# ESP32_Watch-2_01_inch_V1_0.net
KiCad netlist of a schematic drawn in EAGLE
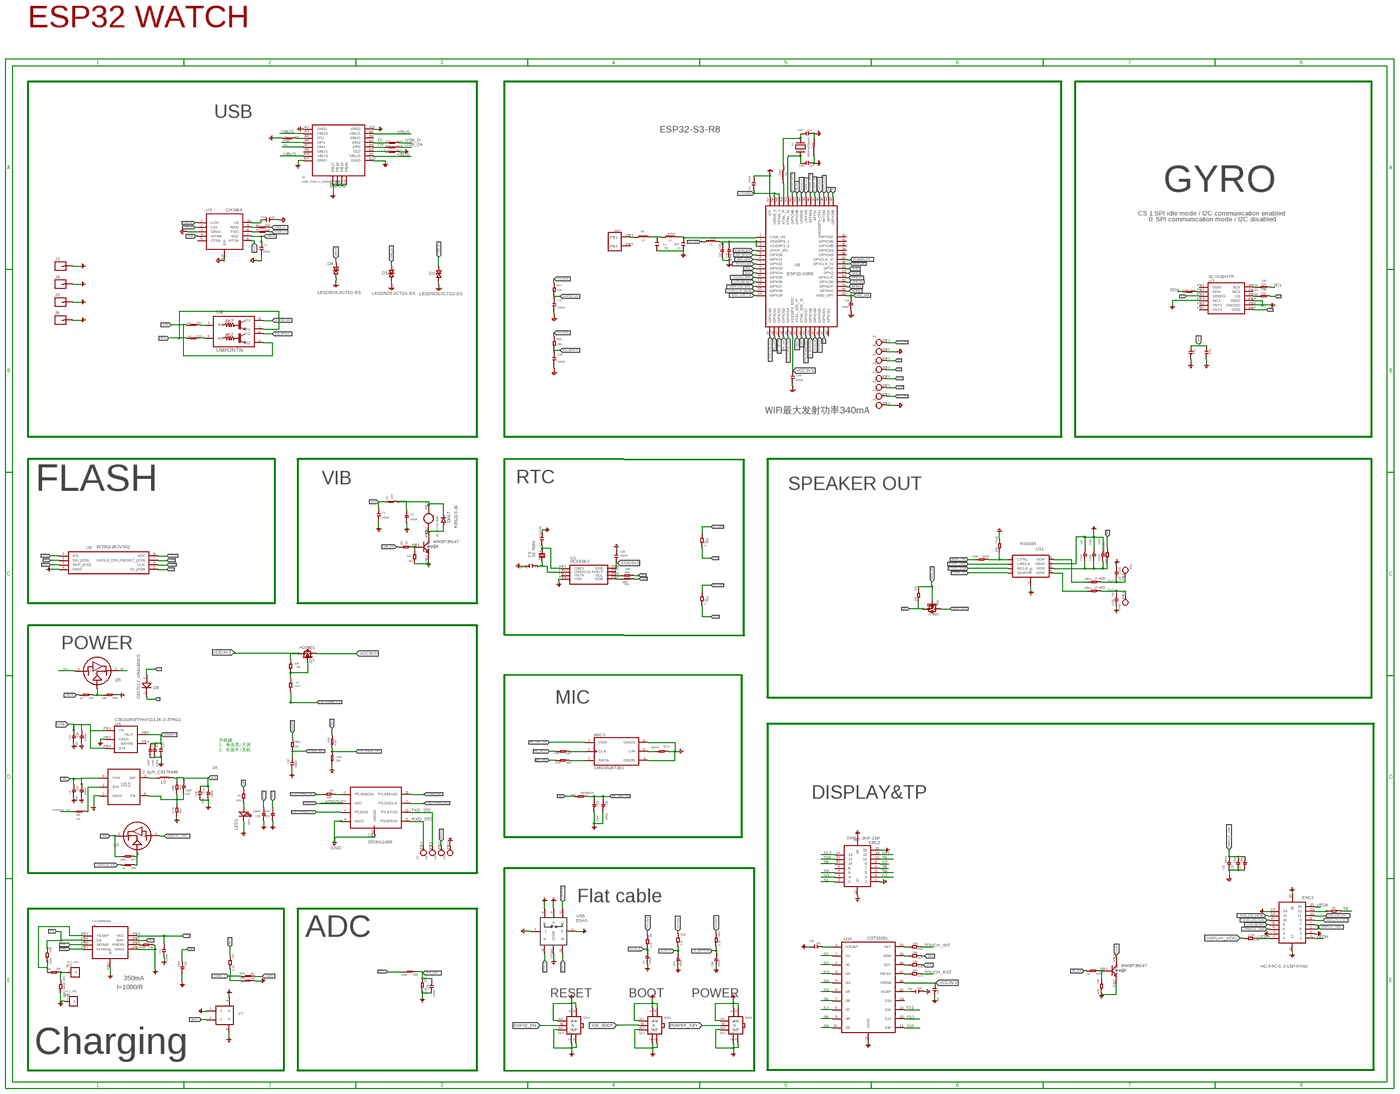
[diagram p0: schematic, sheet 1, overview]
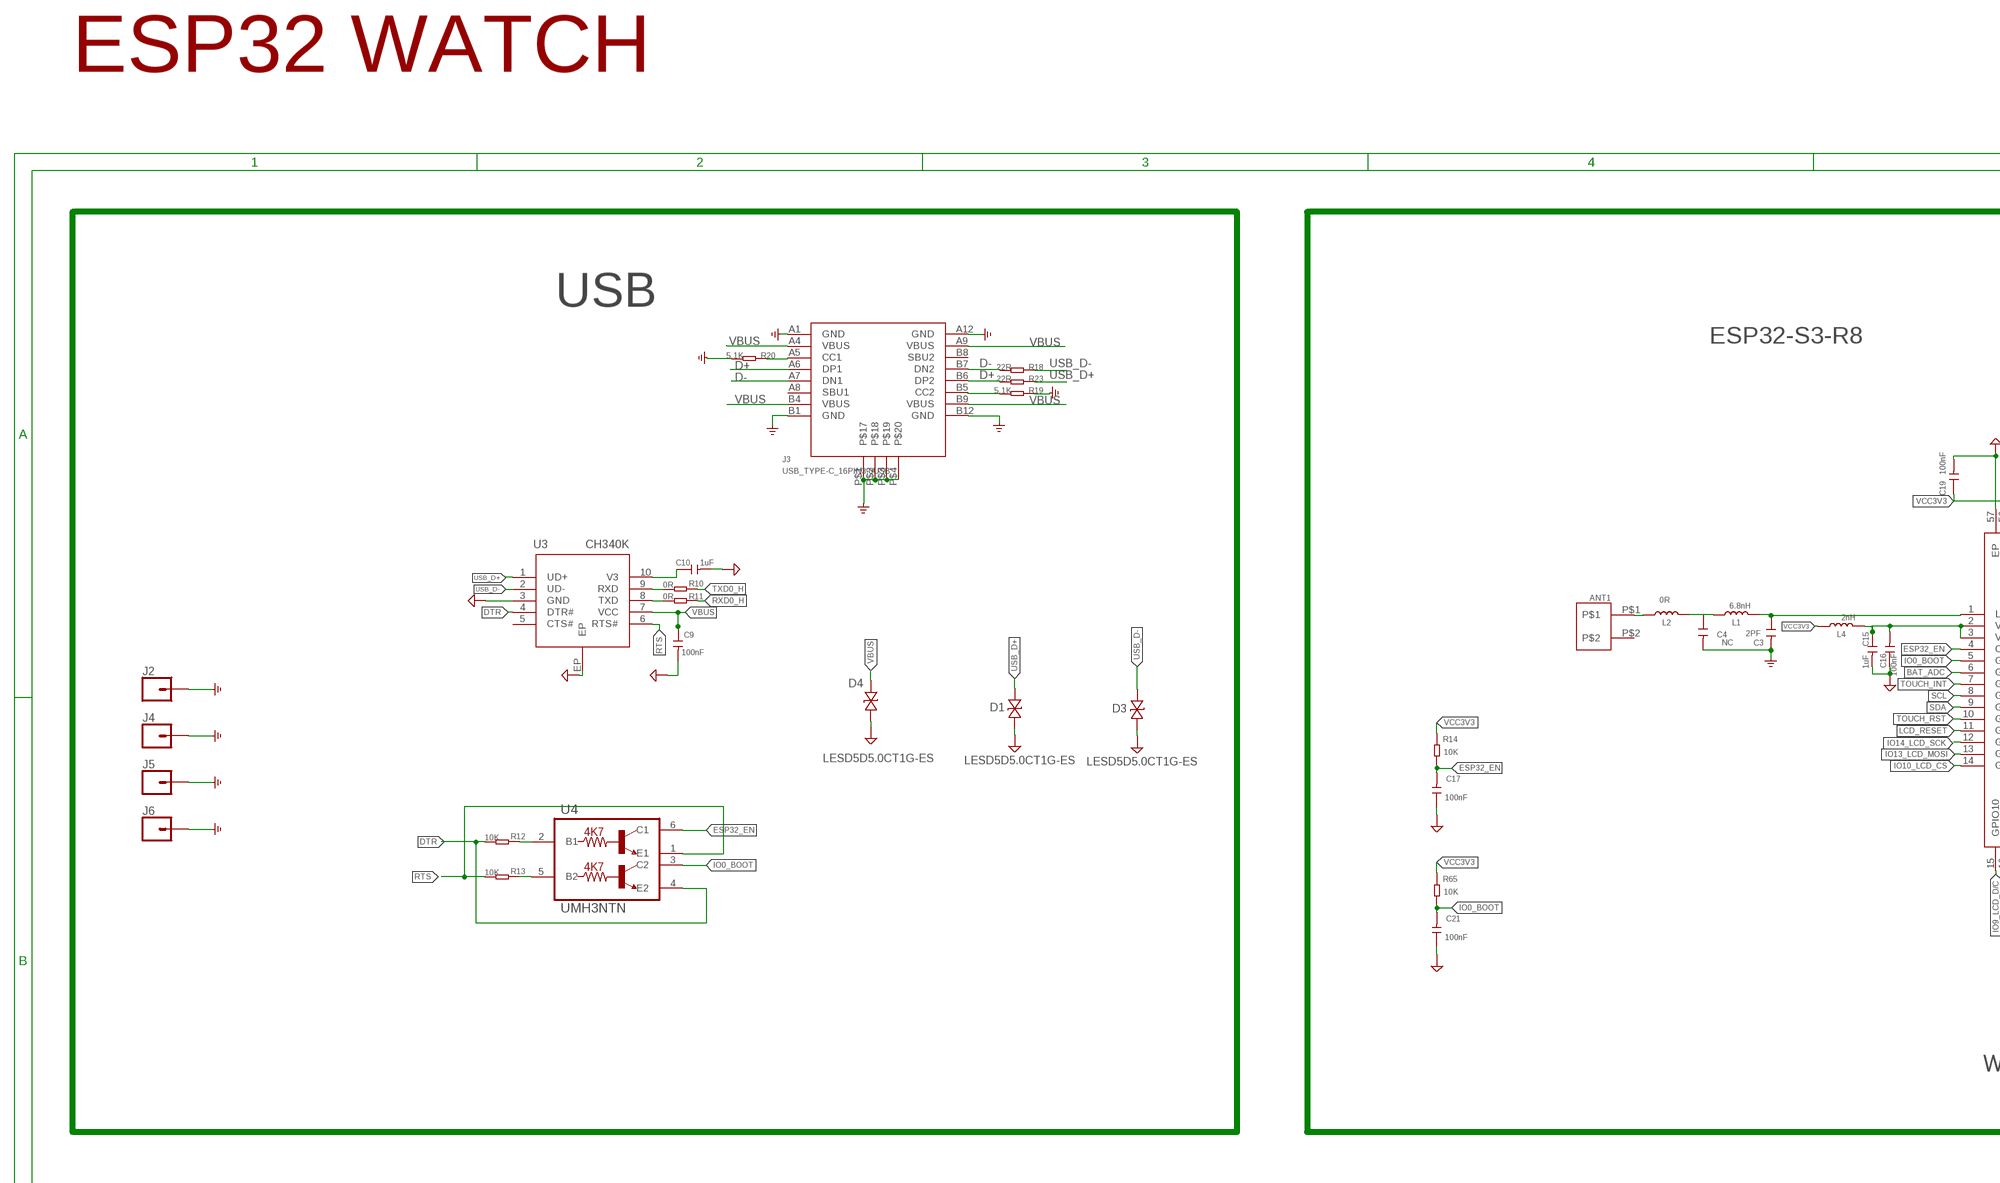
[diagram p1: schematic, sheet 1, part 1 of 4]
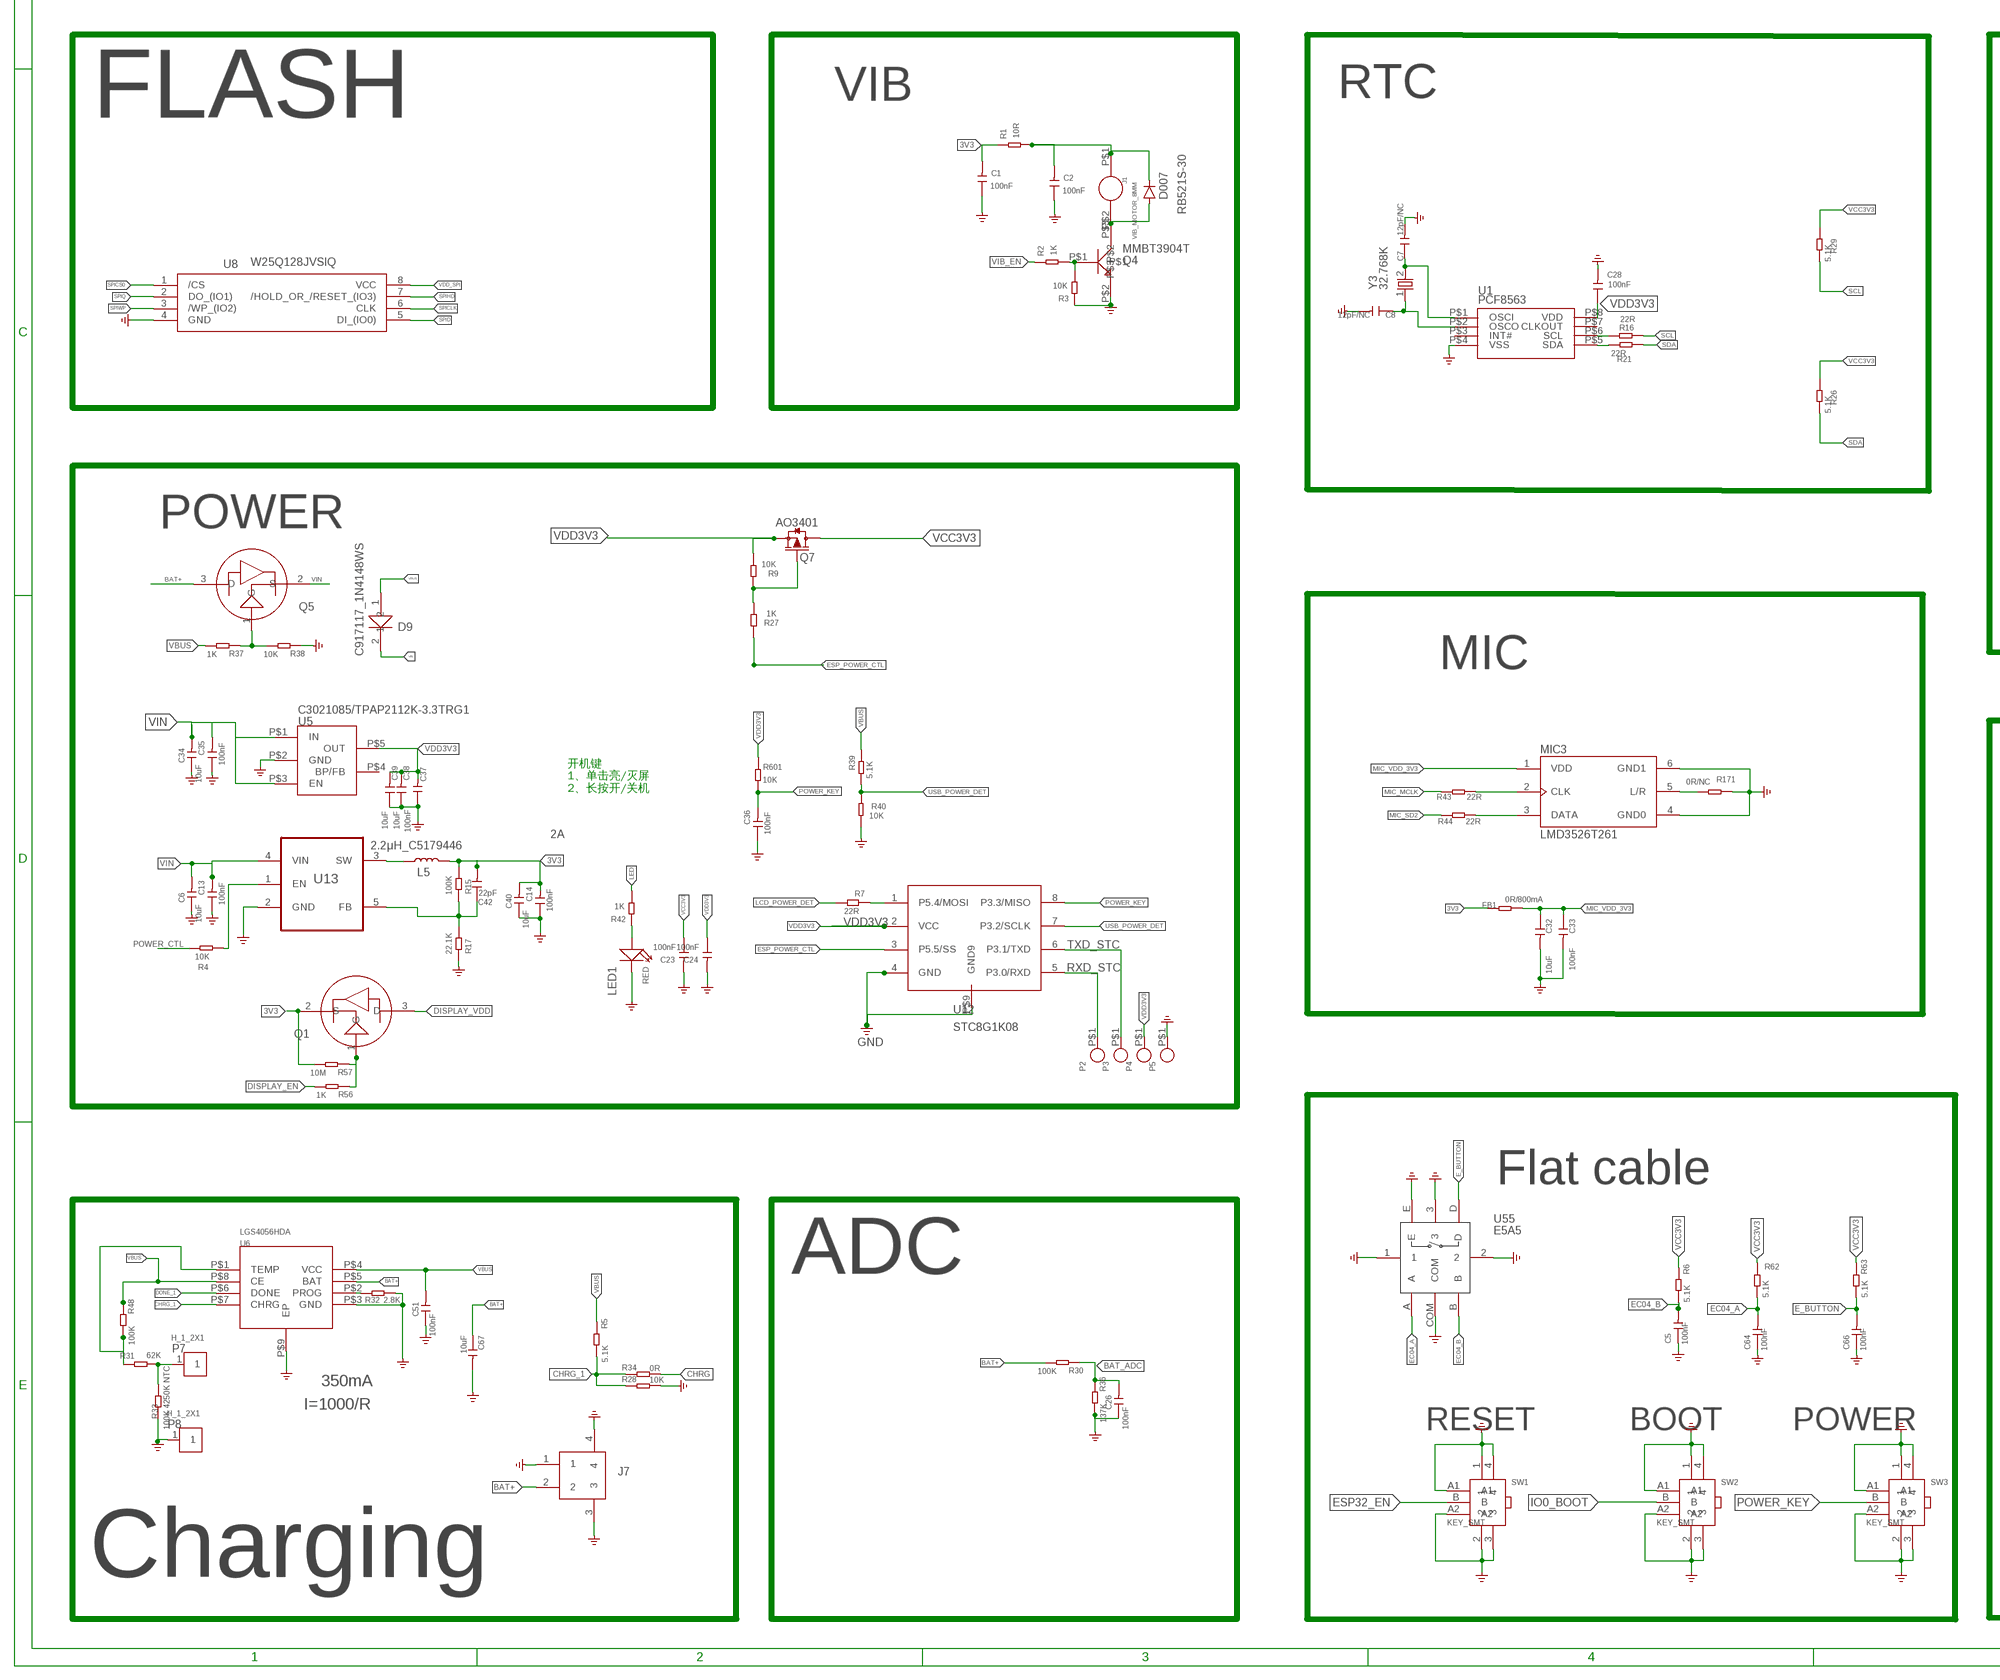
[diagram p2: schematic, sheet 1, part 2 of 4]
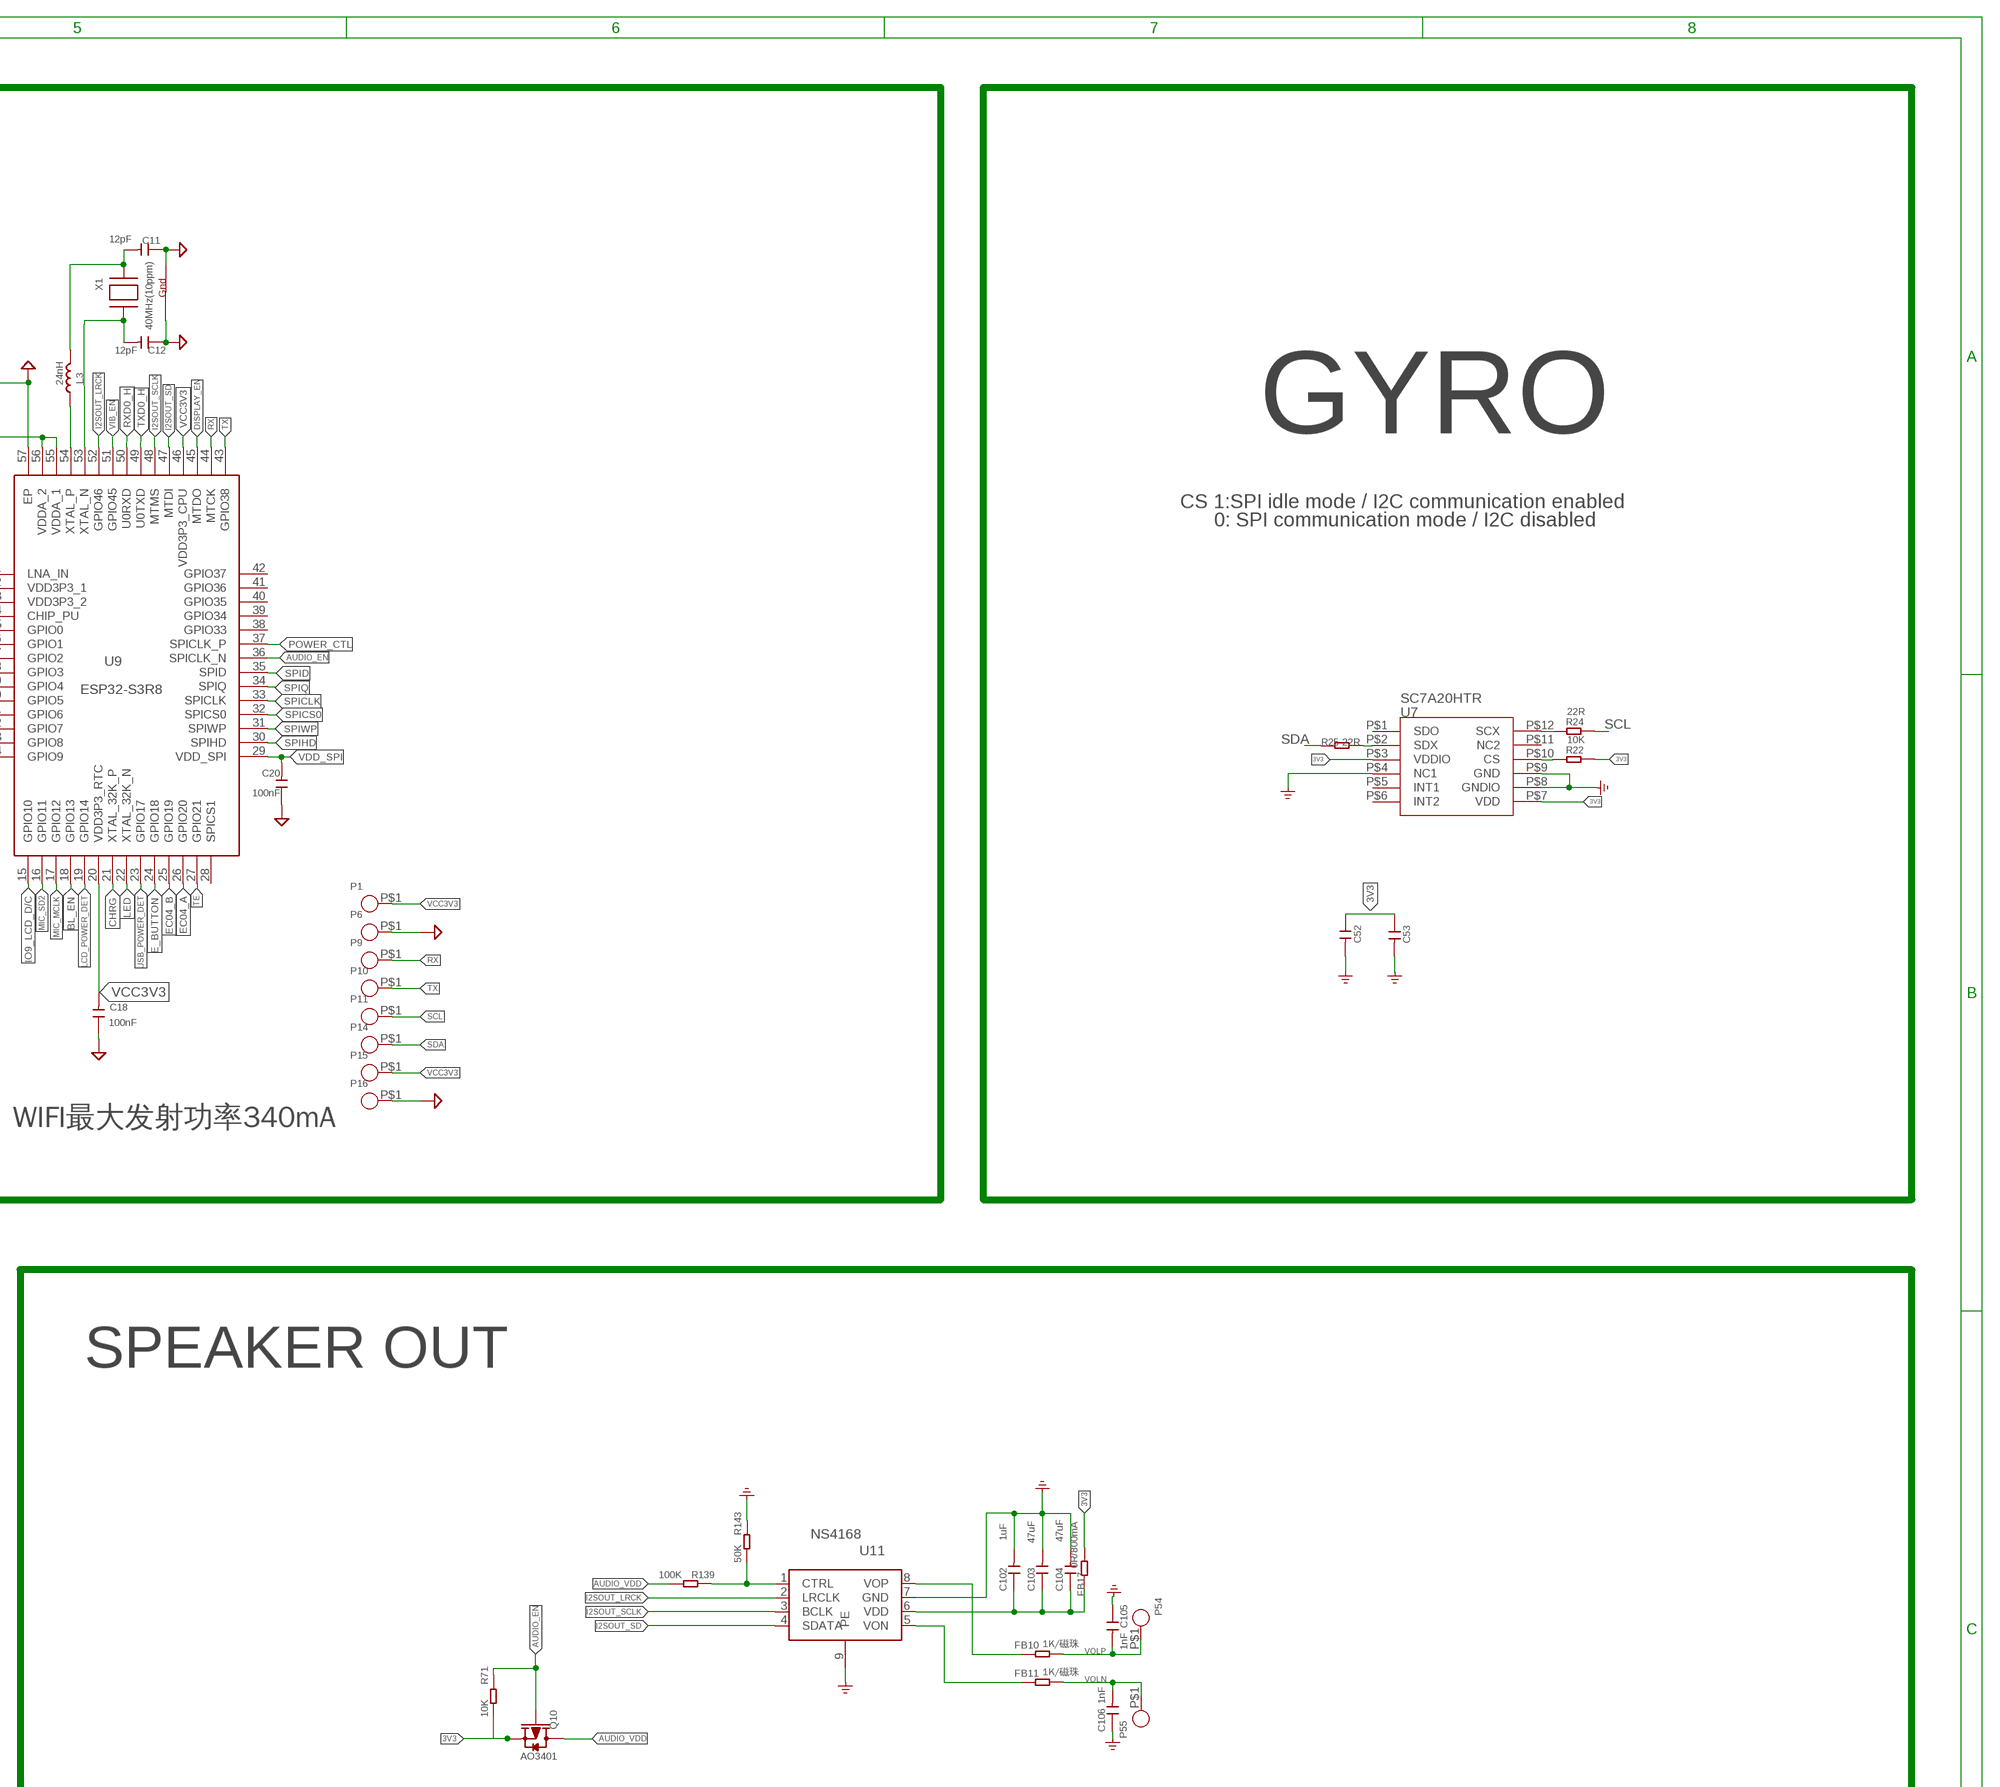
[diagram p3: schematic, sheet 1, part 3 of 4]
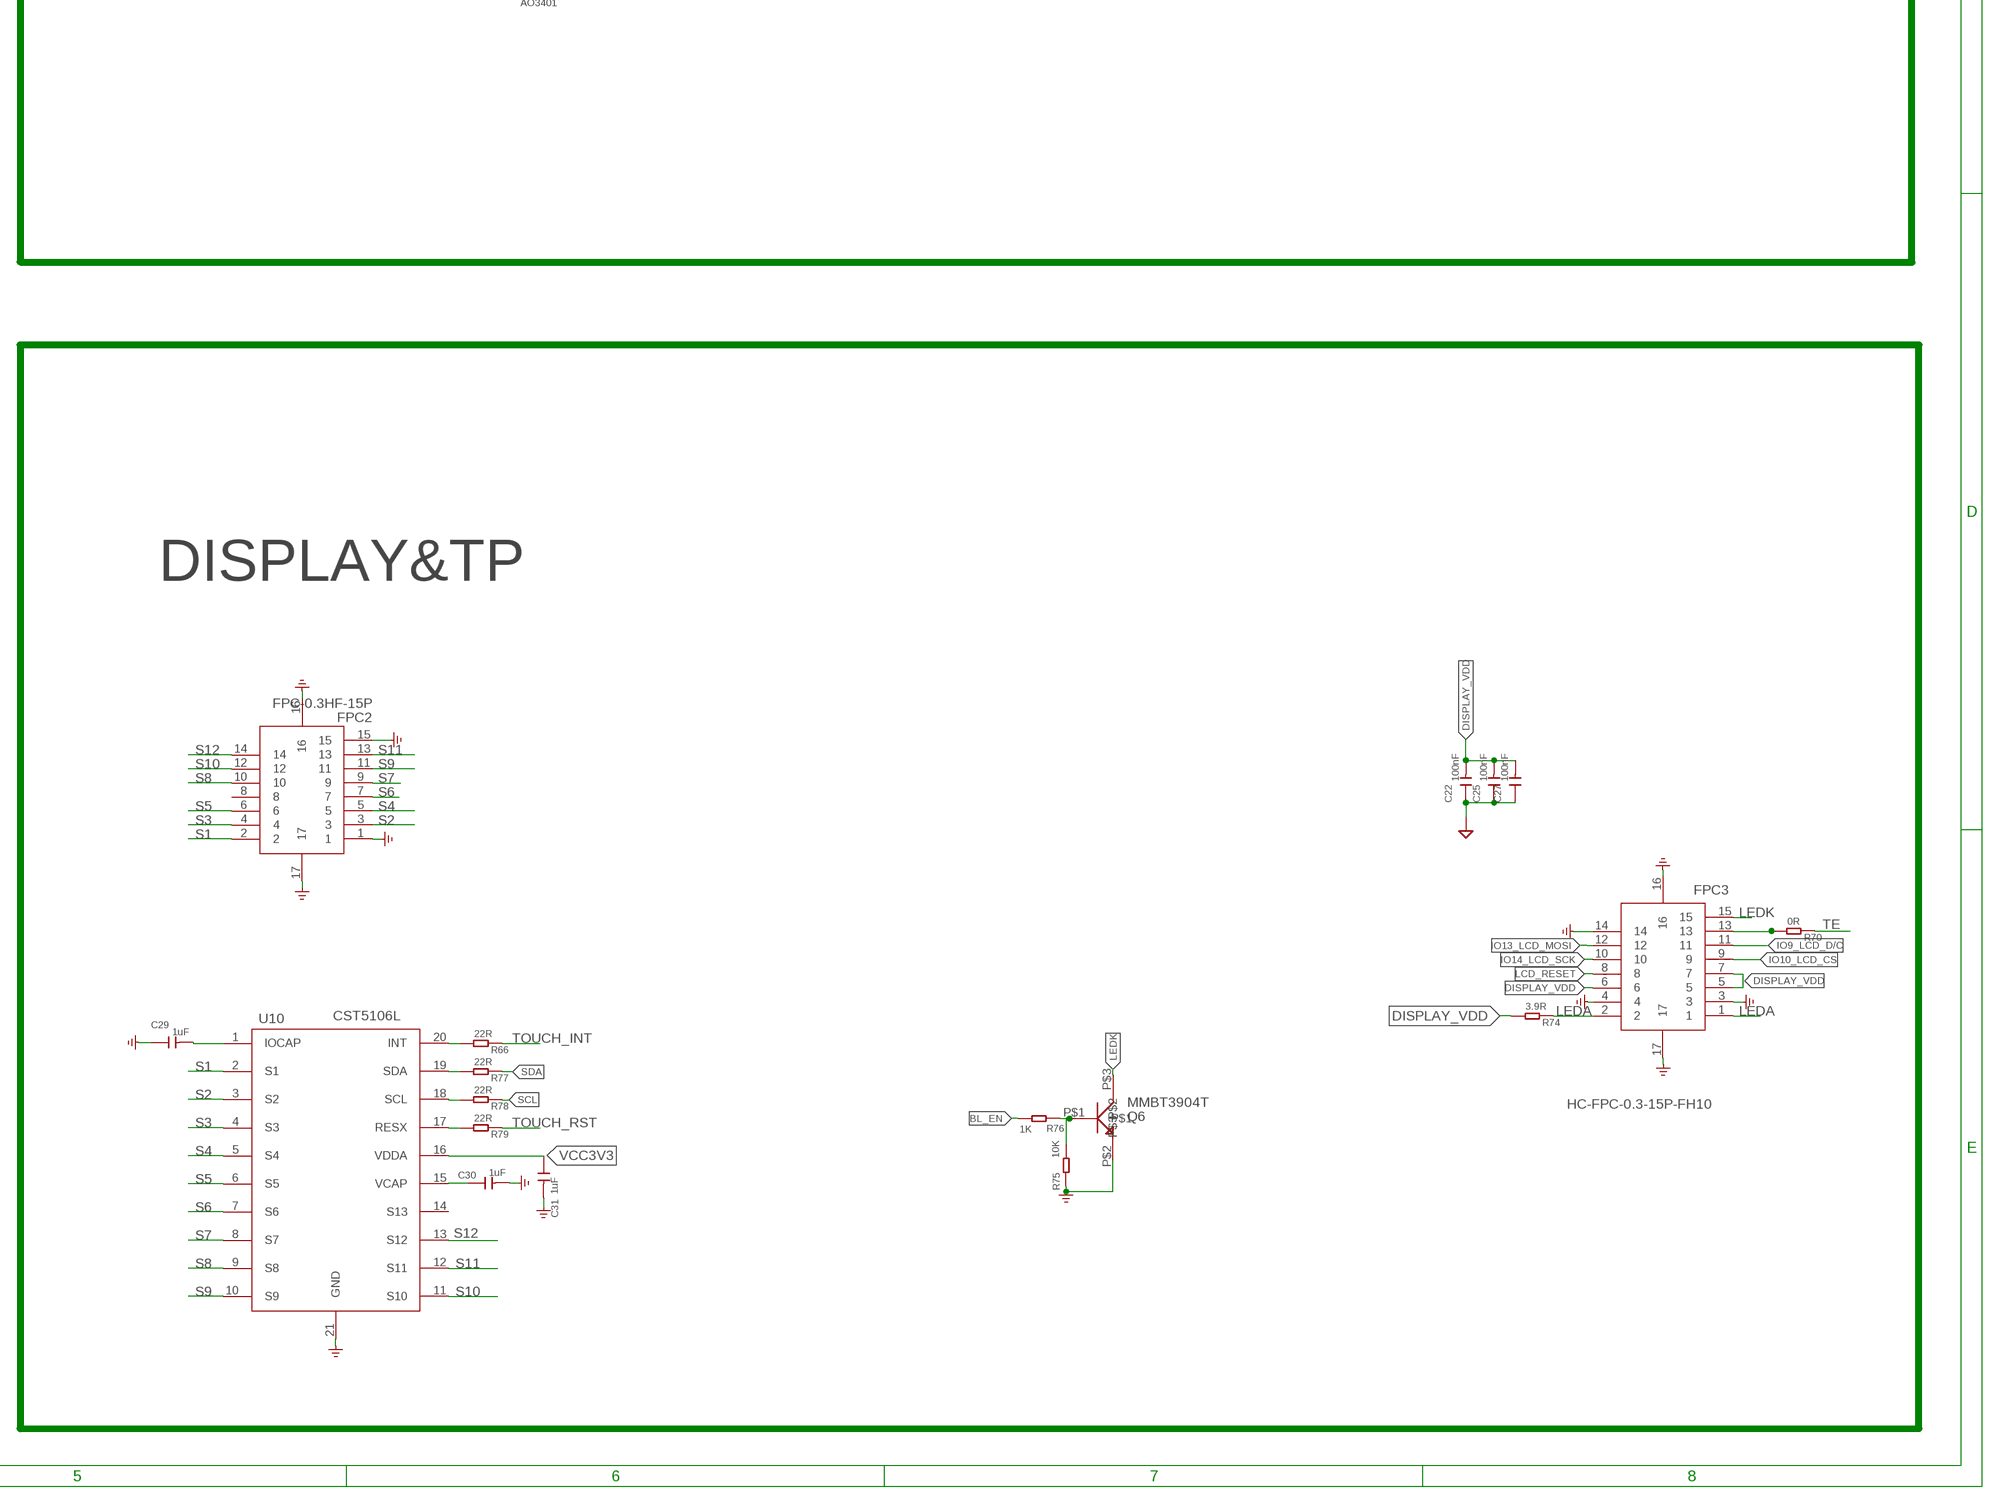
[diagram p4: schematic, sheet 1, part 4 of 4]

(export (version "E")
  (design (tool "Eeschema 10.0.6"))
  (components
    (comp (ref "ANT1")
      (value "OA-D3")
      (footprint "eagle-import:OA-D3")
      (libsource (lib "eagle-import") (part "OA-D3"))
    )
    (comp (ref "C1")
      (value "100nF")
      (footprint "eagle-import:C0402")
      (libsource (lib "eagle-import") (part "CAPC0402-1"))
    )
    (comp (ref "C2")
      (value "100nF")
      (footprint "eagle-import:C0402")
      (libsource (lib "eagle-import") (part "CAPC0402-1"))
    )
    (comp (ref "C3")
      (value "2PF")
      (footprint "eagle-import:C0402")
      (libsource (lib "eagle-import") (part "RC_CAP-0402"))
    )
    (comp (ref "C4")
      (value "NC")
      (footprint "eagle-import:C0402")
      (libsource (lib "eagle-import") (part "RC_CAP-0402"))
    )
    (comp (ref "C5")
      (value "100nF")
      (footprint "eagle-import:C0402")
      (libsource (lib "eagle-import") (part "CAP-0402"))
    )
    (comp (ref "C6")
      (value "10uF")
      (footprint "eagle-import:C0402")
      (libsource (lib "eagle-import") (part "CAP-0402"))
    )
    (comp (ref "C7")
      (value "12pF/NC")
      (footprint "eagle-import:C0402")
      (libsource (lib "eagle-import") (part "CAP-0402"))
    )
    (comp (ref "C8")
      (value "12pF/NC")
      (footprint "eagle-import:C0402")
      (libsource (lib "eagle-import") (part "CAP-0402"))
    )
    (comp (ref "C9")
      (value "100nF")
      (footprint "eagle-import:C0402")
      (libsource (lib "eagle-import") (part "CAPC0402-1"))
    )
    (comp (ref "C10")
      (value "1uF")
      (footprint "eagle-import:C0402")
      (libsource (lib "eagle-import") (part "CAPC0402-1"))
    )
    (comp (ref "C11")
      (value "12pF")
      (footprint "eagle-import:C0402")
      (libsource (lib "eagle-import") (part "CAPC0402-1"))
    )
    (comp (ref "C12")
      (value "12pF")
      (footprint "eagle-import:C0402")
      (libsource (lib "eagle-import") (part "CAPC0402-1"))
    )
    (comp (ref "C13")
      (value "100nF")
      (footprint "eagle-import:C0402")
      (libsource (lib "eagle-import") (part "CAP-0402"))
    )
    (comp (ref "C14")
      (value "100nF")
      (footprint "eagle-import:C0402")
      (libsource (lib "eagle-import") (part "CAP-0402"))
    )
    (comp (ref "C15")
      (value "1uF")
      (footprint "eagle-import:C0402")
      (libsource (lib "eagle-import") (part "CAPC0402-1"))
    )
    (comp (ref "C16")
      (value "100nF")
      (footprint "eagle-import:C0402")
      (libsource (lib "eagle-import") (part "CAPC0402-1"))
    )
    (comp (ref "C17")
      (value "100nF")
      (footprint "eagle-import:C0402")
      (libsource (lib "eagle-import") (part "CAPC0402-1"))
    )
    (comp (ref "C18")
      (value "100nF")
      (footprint "eagle-import:C0402")
      (libsource (lib "eagle-import") (part "CAPC0402-1"))
    )
    (comp (ref "C19")
      (value "100nF")
      (footprint "eagle-import:C0402")
      (libsource (lib "eagle-import") (part "CAPC0402-1"))
    )
    (comp (ref "C20")
      (value "100nF")
      (footprint "eagle-import:C0402")
      (libsource (lib "eagle-import") (part "CAPC0402-1"))
    )
    (comp (ref "C21")
      (value "100nF")
      (footprint "eagle-import:C0402")
      (libsource (lib "eagle-import") (part "CAPC0402-1"))
    )
    (comp (ref "C22")
      (value "100nF")
      (footprint "eagle-import:C0402")
      (libsource (lib "eagle-import") (part "CAPC0402-1"))
    )
    (comp (ref "C23")
      (value "100nF")
      (footprint "eagle-import:C0402")
      (libsource (lib "eagle-import") (part "CAPC0402-1"))
    )
    (comp (ref "C24")
      (value "100nF")
      (footprint "eagle-import:C0402")
      (libsource (lib "eagle-import") (part "CAPC0402-1"))
    )
    (comp (ref "C25")
      (value "100nF")
      (footprint "eagle-import:C0402")
      (libsource (lib "eagle-import") (part "CAPC0402-1"))
    )
    (comp (ref "C26")
      (value "100nF")
      (footprint "eagle-import:C0402")
      (libsource (lib "eagle-import") (part "CAP-0402"))
    )
    (comp (ref "C27")
      (value "100nF")
      (footprint "eagle-import:C0402")
      (libsource (lib "eagle-import") (part "CAPC0402-1"))
    )
    (comp (ref "C28")
      (value "100nF")
      (footprint "eagle-import:C0402")
      (libsource (lib "eagle-import") (part "CAPC0402-1"))
    )
    (comp (ref "C29")
      (value "1uF")
      (footprint "eagle-import:C0402")
      (libsource (lib "eagle-import") (part "CAPC0402-1"))
    )
    (comp (ref "C30")
      (value "1uF")
      (footprint "eagle-import:C0402")
      (libsource (lib "eagle-import") (part "CAPC0402-1"))
    )
    (comp (ref "C31")
      (value "1uF")
      (footprint "eagle-import:C0402")
      (libsource (lib "eagle-import") (part "CAPC0402-1"))
    )
    (comp (ref "C32")
      (value "10uF")
      (footprint "eagle-import:C0402@1")
      (libsource (lib "eagle-import") (part "C0402C0402-1"))
    )
    (comp (ref "C33")
      (value "100nF")
      (footprint "eagle-import:C0402@1")
      (libsource (lib "eagle-import") (part "C0402C0402-1"))
    )
    (comp (ref "C34")
      (value "10uF")
      (footprint "eagle-import:C0402")
      (libsource (lib "eagle-import") (part "CAP-0402"))
    )
    (comp (ref "C35")
      (value "100nF")
      (footprint "eagle-import:C0402")
      (libsource (lib "eagle-import") (part "CAP-0402"))
    )
    (comp (ref "C36")
      (value "100nF")
      (footprint "eagle-import:C0402")
      (libsource (lib "eagle-import") (part "CAP-0402"))
    )
    (comp (ref "C37")
      (value "100nF")
      (footprint "eagle-import:C0402")
      (libsource (lib "eagle-import") (part "CAP-0402"))
    )
    (comp (ref "C38")
      (value "10uF")
      (footprint "eagle-import:C0402")
      (libsource (lib "eagle-import") (part "CAP-0402"))
    )
    (comp (ref "C39")
      (value "10uF")
      (footprint "eagle-import:C0402")
      (libsource (lib "eagle-import") (part "CAP-0402"))
    )
    (comp (ref "C40")
      (value "10uF")
      (footprint "eagle-import:C0402")
      (libsource (lib "eagle-import") (part "CAP-0402"))
    )
    (comp (ref "C42")
      (value "22pF")
      (footprint "eagle-import:C0402")
      (libsource (lib "eagle-import") (part "RC_CAP"))
    )
    (comp (ref "C51")
      (value "100nF")
      (footprint "eagle-import:C0402")
      (libsource (lib "eagle-import") (part "CAP-0402"))
    )
    (comp (ref "C52")
      (value "100nF")
      (footprint "eagle-import:C0402")
      (libsource (lib "eagle-import") (part "CAP-0402"))
    )
    (comp (ref "C53")
      (value "100nF")
      (footprint "eagle-import:C0402")
      (libsource (lib "eagle-import") (part "CAP-0402"))
    )
    (comp (ref "C64")
      (value "100nF")
      (footprint "eagle-import:C0402")
      (libsource (lib "eagle-import") (part "CAP-0402"))
    )
    (comp (ref "C66")
      (value "100nF")
      (footprint "eagle-import:C0402")
      (libsource (lib "eagle-import") (part "CAP-0402"))
    )
    (comp (ref "C67")
      (value "10uF")
      (footprint "eagle-import:DISCRETE-NEW_C0402")
      (libsource (lib "eagle-import") (part "DISCRETE-NEW_CAP-0402"))
    )
    (comp (ref "C102")
      (value "1uF")
      (footprint "eagle-import:C0402@1")
      (libsource (lib "eagle-import") (part "C0402C0402-1"))
    )
    (comp (ref "C103")
      (value "47uF")
      (footprint "eagle-import:C0402")
      (libsource (lib "eagle-import") (part "RC_CAP-0402"))
    )
    (comp (ref "C104")
      (value "47uF")
      (footprint "eagle-import:C0402")
      (libsource (lib "eagle-import") (part "RC_CAP-0402"))
    )
    (comp (ref "C105")
      (value "1nF")
      (footprint "eagle-import:C0402@1")
      (libsource (lib "eagle-import") (part "C0402C0402-1"))
    )
    (comp (ref "C106")
      (value "1nF")
      (footprint "eagle-import:C0402@1")
      (libsource (lib "eagle-import") (part "C0402C0402-1"))
    )
    (comp (ref "D1")
      (value "LESD5D5.0CT1G-ES")
      (footprint "eagle-import:SOD-523_L1.2-W0.8-LS1.6-BI")
      (libsource (lib "eagle-import") (part "LESD5D5.0CT1G-ES"))
    )
    (comp (ref "D3")
      (value "LESD5D5.0CT1G-ES")
      (footprint "eagle-import:SOD-523_L1.2-W0.8-LS1.6-BI")
      (libsource (lib "eagle-import") (part "LESD5D5.0CT1G-ES"))
    )
    (comp (ref "D4")
      (value "LESD5D5.0CT1G-ES")
      (footprint "eagle-import:SOD-523_L1.2-W0.8-LS1.6-BI")
      (libsource (lib "eagle-import") (part "LESD5D5.0CT1G-ES"))
    )
    (comp (ref "D007")
      (value "RB521S-30")
      (footprint "eagle-import:SOD523")
      (libsource (lib "eagle-import") (part "D-SOD523"))
    )
    (comp (ref "D9")
      (value "C917117_1N4148WS")
      (footprint "eagle-import:PICO-2.4_SOD-323")
      (libsource (lib "eagle-import") (part "PICO-2.4_SOD-323"))
    )
    (comp (ref "FB1")
      (value "0R/800mA")
      (footprint "eagle-import:R0402")
      (libsource (lib "eagle-import") (part "R0402-0402"))
    )
    (comp (ref "FB10")
      (value "1K/磁珠")
      (footprint "eagle-import:R0402")
      (libsource (lib "eagle-import") (part "R0402-0402"))
    )
    (comp (ref "FB11")
      (value "1K/磁珠")
      (footprint "eagle-import:R0402")
      (libsource (lib "eagle-import") (part "R0402-0402"))
    )
    (comp (ref "FB17")
      (value "0R/800mA")
      (footprint "eagle-import:R0402")
      (libsource (lib "eagle-import") (part "R0402-0402"))
    )
    (comp (ref "FPC2")
      (value "FPC-0.3HF-15P")
      (footprint "eagle-import:FPC-0.3HF-15P")
      (libsource (lib "eagle-import") (part "FPC-0.3HF-15P"))
    )
    (comp (ref "FPC3")
      (value "HC-FPC-0.3-15P-FH10")
      (footprint "eagle-import:FPC-SMD_HC-FPC-0.3-15P-FH10")
      (libsource (lib "eagle-import") (part "HC-FPC-0.3-15P-FH10"))
    )
    (comp (ref "J1")
      (value "VIB_MOTOR_8MM")
      (footprint "eagle-import:VIB_MOTOR_8MM")
      (libsource (lib "eagle-import") (part "VIB_MOTOR_8MM"))
    )
    (comp (ref "J2")
      (value "CONN_011X01_2.6MM")
      (footprint "eagle-import:1X01_2.5MM")
      (libsource (lib "eagle-import") (part "CONN_011X01_2.6MM"))
    )
    (comp (ref "J3")
      (value "USB_TYPE-C_16PIN3.0USB")
      (footprint "eagle-import:KEVIN_3.0TYPEC-SMD")
      (libsource (lib "eagle-import") (part "USB_TYPE-C_16PIN3.0USB"))
    )
    (comp (ref "J4")
      (value "CONN_011X01_2.6MM")
      (footprint "eagle-import:1X01_2.5MM")
      (libsource (lib "eagle-import") (part "CONN_011X01_2.6MM"))
    )
    (comp (ref "J5")
      (value "CONN_011X01_2.6MM")
      (footprint "eagle-import:1X01_2.5MM")
      (libsource (lib "eagle-import") (part "CONN_011X01_2.6MM"))
    )
    (comp (ref "J6")
      (value "CONN_011X01_2.6MM")
      (footprint "eagle-import:1X01_2.5MM")
      (libsource (lib "eagle-import") (part "CONN_011X01_2.6MM"))
    )
    (comp (ref "J7")
      (value "ZX-SH1.0-2PLT1")
      (footprint "eagle-import:CONN-SMD_2P-P1.00_XUNPU_WAFER-SH1.0-2PWB")
      (libsource (lib "eagle-import") (part "ZX-SH1.0-2PLT1"))
    )
    (comp (ref "L1")
      (value "6.8nH")
      (footprint "eagle-import:L0402")
      (libsource (lib "eagle-import") (part "RC_L0402"))
    )
    (comp (ref "L2")
      (value "0R")
      (footprint "eagle-import:L0402")
      (libsource (lib "eagle-import") (part "RC_L0402"))
    )
    (comp (ref "L3")
      (value "24nH")
      (footprint "eagle-import:L0402")
      (libsource (lib "eagle-import") (part "RC_L0402"))
    )
    (comp (ref "L4")
      (value "2nH")
      (footprint "eagle-import:L0402")
      (libsource (lib "eagle-import") (part "L0402"))
    )
    (comp (ref "L5")
      (value "2.2μH_C5179446")
      (footprint "eagle-import:1008(2520)")
      (libsource (lib "eagle-import") (part "4.7μH_SHIELDED_INDUCTOR"))
    )
    (comp (ref "LED1")
      (value "RED")
      (footprint "eagle-import:LED-0603")
      (libsource (lib "eagle-import") (part "LED'0603'"))
    )
    (comp (ref "MIC3")
      (value "LMD3526T261")
      (footprint "eagle-import:SMD_6P_3.5X2.7MM")
      (libsource (lib "eagle-import") (part "LMD3526T261"))
    )
    (comp (ref "P1")
      (value "TEST_PADPAD-1.5MM")
      (footprint "eagle-import:TEST_PAD-1.5MM")
      (libsource (lib "eagle-import") (part "TEST_PADPAD-1.5MM"))
    )
    (comp (ref "P2")
      (value "TEST_PADPAD-1.5MM")
      (footprint "eagle-import:TEST_PAD-1.5MM")
      (libsource (lib "eagle-import") (part "RC_TEST_PADPAD-1.5MM"))
    )
    (comp (ref "P3")
      (value "TEST_PADPAD-1.5MM")
      (footprint "eagle-import:TEST_PAD-1.5MM")
      (libsource (lib "eagle-import") (part "RC_TEST_PADPAD-1.5MM"))
    )
    (comp (ref "P4")
      (value "TEST_PADPAD-1.5MM")
      (footprint "eagle-import:TEST_PAD-1.5MM")
      (libsource (lib "eagle-import") (part "RC_TEST_PADPAD-1.5MM"))
    )
    (comp (ref "P5")
      (value "TEST_PADPAD-1.5MM")
      (footprint "eagle-import:TEST_PAD-1.5MM")
      (libsource (lib "eagle-import") (part "RC_TEST_PADPAD-1.5MM"))
    )
    (comp (ref "P6")
      (value "TEST_PADPAD-1.5MM")
      (footprint "eagle-import:TEST_PAD-1.5MM")
      (libsource (lib "eagle-import") (part "TEST_PADPAD-1.5MM"))
    )
    (comp (ref "P7")
      (value "H_1_2X1")
      (footprint "eagle-import:H_1_2X1")
      (libsource (lib "eagle-import") (part "H_1_2X1"))
    )
    (comp (ref "P8")
      (value "H_1_2X1")
      (footprint "eagle-import:H_1_2X1")
      (libsource (lib "eagle-import") (part "H_1_2X1"))
    )
    (comp (ref "P9")
      (value "TEST_PADPAD-1.5MM")
      (footprint "eagle-import:TEST_PAD-1.5MM")
      (libsource (lib "eagle-import") (part "TEST_PADPAD-1.5MM"))
    )
    (comp (ref "P10")
      (value "TEST_PADPAD-1.5MM")
      (footprint "eagle-import:TEST_PAD-1.5MM")
      (libsource (lib "eagle-import") (part "TEST_PADPAD-1.5MM"))
    )
    (comp (ref "P11")
      (value "TEST_PADPAD-1.5MM")
      (footprint "eagle-import:TEST_PAD-1.5MM")
      (libsource (lib "eagle-import") (part "TEST_PADPAD-1.5MM"))
    )
    (comp (ref "P14")
      (value "TEST_PADPAD-1.5MM")
      (footprint "eagle-import:TEST_PAD-1.5MM")
      (libsource (lib "eagle-import") (part "TEST_PADPAD-1.5MM"))
    )
    (comp (ref "P15")
      (value "TEST_PADPAD-1.5MM")
      (footprint "eagle-import:TEST_PAD-1.5MM")
      (libsource (lib "eagle-import") (part "TEST_PADPAD-1.5MM"))
    )
    (comp (ref "P16")
      (value "TEST_PADPAD-1.5MM")
      (footprint "eagle-import:TEST_PAD-1.5MM")
      (libsource (lib "eagle-import") (part "TEST_PADPAD-1.5MM"))
    )
    (comp (ref "P54")
      (value "TEST_PADPAD-1.5MM")
      (footprint "eagle-import:TEST_PAD-1.5MM")
      (libsource (lib "eagle-import") (part "TEST_PADPAD-1.5MM"))
    )
    (comp (ref "P55")
      (value "TEST_PADPAD-1.5MM")
      (footprint "eagle-import:TEST_PAD-1.5MM")
      (libsource (lib "eagle-import") (part "TEST_PADPAD-1.5MM"))
    )
    (comp (ref "Q1")
      (value "SI2301")
      (footprint "eagle-import:DFN8_SOT-23")
      (libsource (lib "eagle-import") (part "DFN8_P-MOS-SOT23"))
    )
    (comp (ref "Q4")
      (value "MMBT3904T")
      (footprint "eagle-import:SOT-523")
      (libsource (lib "eagle-import") (part "MMBT3904T-JSM"))
    )
    (comp (ref "Q5")
      (value "SI2301")
      (footprint "eagle-import:DFN8_SOT-23")
      (libsource (lib "eagle-import") (part "DFN8_P-MOS-SOT23"))
    )
    (comp (ref "Q6")
      (value "MMBT3904T")
      (footprint "eagle-import:SOT-523")
      (libsource (lib "eagle-import") (part "MMBT3904T-JSM"))
    )
    (comp (ref "Q7")
      (value "AO3401")
      (footprint "eagle-import:PMOS_SOT23")
      (libsource (lib "eagle-import") (part "MOSFET-PSOT23"))
    )
    (comp (ref "Q10")
      (value "AO3401")
      (footprint "eagle-import:PMOS_SOT23")
      (libsource (lib "eagle-import") (part "CrowPanel_Advance_HMI_MOSFET-PSOT23"))
    )
    (comp (ref "R1")
      (value "10R")
      (footprint "eagle-import:R0402")
      (libsource (lib "eagle-import") (part "RES-0402"))
    )
    (comp (ref "R2")
      (value "1K")
      (footprint "eagle-import:R0402")
      (libsource (lib "eagle-import") (part "RES-0402"))
    )
    (comp (ref "R3")
      (value "10K")
      (footprint "eagle-import:R0402")
      (libsource (lib "eagle-import") (part "RES-0402"))
    )
    (comp (ref "R4")
      (value "10K")
      (footprint "eagle-import:R0402")
      (libsource (lib "eagle-import") (part "RES-0402"))
    )
    (comp (ref "R5")
      (value "5.1K")
      (footprint "eagle-import:R0402")
      (libsource (lib "eagle-import") (part "RES0402"))
    )
    (comp (ref "R6")
      (value "5.1K")
      (footprint "eagle-import:R0402")
      (libsource (lib "eagle-import") (part "RES0402"))
    )
    (comp (ref "R7")
      (value "22R")
      (footprint "eagle-import:R0402")
      (libsource (lib "eagle-import") (part "RESR0402"))
    )
    (comp (ref "R9")
      (value "10K")
      (footprint "eagle-import:R0402")
      (libsource (lib "eagle-import") (part "RESR0402"))
    )
    (comp (ref "R10")
      (value "0R")
      (footprint "eagle-import:R0402")
      (libsource (lib "eagle-import") (part "RES-0402"))
    )
    (comp (ref "R11")
      (value "0R")
      (footprint "eagle-import:R0402")
      (libsource (lib "eagle-import") (part "RES-0402"))
    )
    (comp (ref "R12")
      (value "10K")
      (footprint "eagle-import:R0402")
      (libsource (lib "eagle-import") (part "RES-0402"))
    )
    (comp (ref "R13")
      (value "10K")
      (footprint "eagle-import:R0402")
      (libsource (lib "eagle-import") (part "RES-0402"))
    )
    (comp (ref "R14")
      (value "10K")
      (footprint "eagle-import:R0402")
      (libsource (lib "eagle-import") (part "RES-0402"))
    )
    (comp (ref "R15")
      (value "100K")
      (footprint "eagle-import:0402")
      (libsource (lib "eagle-import") (part "R"))
    )
    (comp (ref "R16")
      (value "22R")
      (footprint "eagle-import:R0402")
      (libsource (lib "eagle-import") (part "RES0402"))
    )
    (comp (ref "R17")
      (value "22.1K")
      (footprint "eagle-import:0402")
      (libsource (lib "eagle-import") (part "R"))
    )
    (comp (ref "R18")
      (value "22R")
      (footprint "eagle-import:0402")
      (libsource (lib "eagle-import") (part "R0402-1"))
    )
    (comp (ref "R19")
      (value "5.1K")
      (footprint "eagle-import:0402")
      (libsource (lib "eagle-import") (part "R0402-1"))
    )
    (comp (ref "R20")
      (value "5.1K")
      (footprint "eagle-import:0402")
      (libsource (lib "eagle-import") (part "R0402-1"))
    )
    (comp (ref "R21")
      (value "22R")
      (footprint "eagle-import:R0402")
      (libsource (lib "eagle-import") (part "RES0402"))
    )
    (comp (ref "R22")
      (value "10K")
      (footprint "eagle-import:R0402")
      (libsource (lib "eagle-import") (part "RES0402"))
    )
    (comp (ref "R23")
      (value "22R")
      (footprint "eagle-import:0402")
      (libsource (lib "eagle-import") (part "R0402-1"))
    )
    (comp (ref "R24")
      (value "22R")
      (footprint "eagle-import:R0402")
      (libsource (lib "eagle-import") (part "RES0402"))
    )
    (comp (ref "R25")
      (value "22R")
      (footprint "eagle-import:R0402")
      (libsource (lib "eagle-import") (part "RES0402"))
    )
    (comp (ref "R26")
      (value "5.1K")
      (footprint "eagle-import:R0402")
      (libsource (lib "eagle-import") (part "RES0402"))
    )
    (comp (ref "R27")
      (value "1K")
      (footprint "eagle-import:R0402")
      (libsource (lib "eagle-import") (part "RESR0402"))
    )
    (comp (ref "R28")
      (value "10K")
      (footprint "eagle-import:R0402")
      (libsource (lib "eagle-import") (part "RES0402"))
    )
    (comp (ref "R29")
      (value "5.1K")
      (footprint "eagle-import:R0402")
      (libsource (lib "eagle-import") (part "RES0402"))
    )
    (comp (ref "R30")
      (value "100K")
      (footprint "eagle-import:R0402")
      (libsource (lib "eagle-import") (part "RES0402"))
    )
    (comp (ref "R31")
      (value "62K")
      (footprint "eagle-import:R0402")
      (libsource (lib "eagle-import") (part "RES0402"))
    )
    (comp (ref "R32")
      (value "2.8K")
      (footprint "eagle-import:R0402")
      (libsource (lib "eagle-import") (part "RES0402"))
    )
    (comp (ref "R33")
      (value "100K 4250K NTC")
      (footprint "eagle-import:R0402")
      (libsource (lib "eagle-import") (part "LoraWAN_Gateway_Mainboard_RES-0402"))
    )
    (comp (ref "R34")
      (value "0R")
      (footprint "eagle-import:R0402")
      (libsource (lib "eagle-import") (part "RES0402"))
    )
    (comp (ref "R36")
      (value "137K")
      (footprint "eagle-import:R0402")
      (libsource (lib "eagle-import") (part "RES0402"))
    )
    (comp (ref "R37")
      (value "1K")
      (footprint "eagle-import:R0402")
      (libsource (lib "eagle-import") (part "RES0402"))
    )
    (comp (ref "R38")
      (value "10K")
      (footprint "eagle-import:R0402")
      (libsource (lib "eagle-import") (part "RES0402"))
    )
    (comp (ref "R39")
      (value "5.1K")
      (footprint "eagle-import:R0402")
      (libsource (lib "eagle-import") (part "RESR0402"))
    )
    (comp (ref "R40")
      (value "10K")
      (footprint "eagle-import:R0402")
      (libsource (lib "eagle-import") (part "RESR0402"))
    )
    (comp (ref "R42")
      (value "1K")
      (footprint "eagle-import:R0402")
      (libsource (lib "eagle-import") (part "RES-0402"))
    )
    (comp (ref "R43")
      (value "22R")
      (footprint "eagle-import:R0402")
      (libsource (lib "eagle-import") (part "R0402-0402"))
    )
    (comp (ref "R44")
      (value "22R")
      (footprint "eagle-import:R0402")
      (libsource (lib "eagle-import") (part "R0402-0402"))
    )
    (comp (ref "R48")
      (value "100K")
      (footprint "eagle-import:R0402")
      (libsource (lib "eagle-import") (part "RES0402"))
    )
    (comp (ref "R56")
      (value "1K")
      (footprint "eagle-import:R0402")
      (libsource (lib "eagle-import") (part "RES0402"))
    )
    (comp (ref "R57")
      (value "10M")
      (footprint "eagle-import:R0402")
      (libsource (lib "eagle-import") (part "RES0402"))
    )
    (comp (ref "R62")
      (value "5.1K")
      (footprint "eagle-import:R0402")
      (libsource (lib "eagle-import") (part "RES0402"))
    )
    (comp (ref "R63")
      (value "5.1K")
      (footprint "eagle-import:R0402")
      (libsource (lib "eagle-import") (part "RES0402"))
    )
    (comp (ref "R65")
      (value "10K")
      (footprint "eagle-import:R0402")
      (libsource (lib "eagle-import") (part "RES-0402"))
    )
    (comp (ref "R66")
      (value "22R")
      (footprint "eagle-import:R0402")
      (libsource (lib "eagle-import") (part "RES-0402"))
    )
    (comp (ref "R70")
      (value "0R")
      (footprint "eagle-import:R0402")
      (libsource (lib "eagle-import") (part "RES-0402"))
    )
    (comp (ref "R71")
      (value "10K")
      (footprint "eagle-import:R0402")
      (libsource (lib "eagle-import") (part "R0402-0402"))
    )
    (comp (ref "R74")
      (value "3.9R")
      (footprint "eagle-import:R0402")
      (libsource (lib "eagle-import") (part "RES-0402"))
    )
    (comp (ref "R75")
      (value "10K")
      (footprint "eagle-import:R0402")
      (libsource (lib "eagle-import") (part "RES0402"))
    )
    (comp (ref "R76")
      (value "1K")
      (footprint "eagle-import:R0402")
      (libsource (lib "eagle-import") (part "RES0402"))
    )
    (comp (ref "R77")
      (value "22R")
      (footprint "eagle-import:R0402")
      (libsource (lib "eagle-import") (part "RES-0402"))
    )
    (comp (ref "R78")
      (value "22R")
      (footprint "eagle-import:R0402")
      (libsource (lib "eagle-import") (part "RES-0402"))
    )
    (comp (ref "R79")
      (value "22R")
      (footprint "eagle-import:R0402")
      (libsource (lib "eagle-import") (part "RES-0402"))
    )
    (comp (ref "R139")
      (value "100K")
      (footprint "eagle-import:R0402")
      (libsource (lib "eagle-import") (part "R0402-0402"))
    )
    (comp (ref "R143")
      (value "50K")
      (footprint "eagle-import:R0402")
      (libsource (lib "eagle-import") (part "R0402-0402"))
    )
    (comp (ref "R171")
      (value "0R/NC")
      (footprint "eagle-import:R0402")
      (libsource (lib "eagle-import") (part "R0402-0402"))
    )
    (comp (ref "R601")
      (value "10K")
      (footprint "eagle-import:R0402")
      (libsource (lib "eagle-import") (part "RESR0402"))
    )
    (comp (ref "SW1")
      (value "KEY_SMT")
      (footprint "eagle-import:SMD_4.1X3.2")
      (libsource (lib "eagle-import") (part "KEY_SMT"))
    )
    (comp (ref "SW2")
      (value "KEY_SMT")
      (footprint "eagle-import:SMD_4.1X3.2")
      (libsource (lib "eagle-import") (part "KEY_SMT"))
    )
    (comp (ref "SW3")
      (value "KEY_SMT")
      (footprint "eagle-import:SMD_4.1X3.2")
      (libsource (lib "eagle-import") (part "KEY_SMT"))
    )
    (comp (ref "U1")
      (value "PCF8563")
      (footprint "eagle-import:MSOP-8")
      (libsource (lib "eagle-import") (part "PCF8563MSOP-8"))
    )
    (comp (ref "U3")
      (value "CH340K")
      (footprint "eagle-import:ESOP-10-EP-150MIL")
      (libsource (lib "eagle-import") (part "CH340K"))
    )
    (comp (ref "U4")
      (value "UMH3NTN")
      (footprint "eagle-import:SOP65P210X100-6N")
      (fields (field (name "MF") "Rohm"))
      (libsource (lib "eagle-import") (part "UMH3NTN"))
    )
    (comp (ref "U5")
      (value "C3021085/TPAP2112K-3.3TRG1")
      (footprint "eagle-import:SOT23-5")
      (libsource (lib "eagle-import") (part "SGM2019"))
    )
    (comp (ref "U6")
      (value "LGS4056HDA")
      (footprint "eagle-import:DFN2X2-8")
      (libsource (lib "eagle-import") (part "LGS4056HDA"))
    )
    (comp (ref "U7")
      (value "SC7A20HTR")
      (footprint "eagle-import:LGA-12(2_2)")
      (libsource (lib "eagle-import") (part "SC7A20HTR"))
    )
    (comp (ref "U8")
      (value "W25Q128JVSIQ")
      (footprint "eagle-import:SOIC127P790X216-8N")
      (fields (field (name "MOUSER_PART_NUMBER") "454-W25Q128JVSIQ"))
      (libsource (lib "eagle-import") (part "W25Q128JVSIQ"))
    )
    (comp (ref "U9")
      (value "ESP32-S3R8")
      (footprint "eagle-import:QFN40P700X700X90-57N")
      (fields (field (name "MOUSER_PART_NUMBER") "356-ESP32-S3R8"))
      (libsource (lib "eagle-import") (part "ESP32-S3R8"))
    )
    (comp (ref "U10")
      (value "CST5106L")
      (footprint "eagle-import:QFN20-3_3")
      (libsource (lib "eagle-import") (part "AXS5106L"))
    )
    (comp (ref "U11")
      (value "NS4168")
      (footprint "eagle-import:NS4168-ESOP-8")
      (libsource (lib "eagle-import") (part "NS4168-ESOP-8"))
    )
    (comp (ref "U12")
      (value "STC8G1K08")
      (footprint "eagle-import:DFN8")
      (libsource (lib "eagle-import") (part "STC8G1K08"))
    )
    (comp (ref "U13")
      (value "MT3406_C22462728")
      (footprint "eagle-import:SOT95P280X145-5N")
      (fields (field (name "MF") "Texas Instruments") (field (name "MP") "TLV62569DBVR"))
      (libsource (lib "eagle-import") (part "TLV62569DBVR"))
    )
    (comp (ref "U55")
      (value "E5A5")
      (footprint "eagle-import:E5A5-2.35S10")
      (libsource (lib "eagle-import") (part "E5A5"))
    )
    (comp (ref "X1")
      (value "40MHz(10ppm)")
      (footprint "eagle-import:ADAFRUIT_NX3225")
      (libsource (lib "eagle-import") (part "ADAFRUIT_XTAL-4-3225"))
    )
    (comp (ref "Y3")
      (value "32.768K")
      (footprint "eagle-import:NORDIC_NRF_XTAL_3215_N")
      (libsource (lib "eagle-import") (part "NORDIC_NRF_XTAL_32KHZ"))
    )
  )
  (nets
    (net (code "1") (name "/D+") (class "Default")
      (node (ref "J3") (pin "A6") (pinfunction "DP1_A6") (pintype "bidirectional"))
      (node (ref "J3") (pin "B6") (pinfunction "DP2_B6") (pintype "bidirectional"))
      (node (ref "R23") (pin "2") (pinfunction "2_2") (pintype "passive"))
    )
    (net (code "2") (name "/D-") (class "Default")
      (node (ref "J3") (pin "A7") (pinfunction "DN1_A7") (pintype "bidirectional"))
      (node (ref "J3") (pin "B7") (pinfunction "DN2_B7") (pintype "bidirectional"))
      (node (ref "R18") (pin "2") (pinfunction "2_2") (pintype "passive"))
    )
    (net (code "3") (name "/LEDA") (class "Default")
      (node (ref "FPC3") (pin "1") (pinfunction "1_1") (pintype "bidirectional"))
      (node (ref "FPC3") (pin "2") (pinfunction "2_2") (pintype "bidirectional"))
      (node (ref "R74") (pin "1") (pinfunction "1_1") (pintype "passive"))
    )
    (net (code "4") (name "/RXD_STC") (class "Default")
      (node (ref "P2") (pin "P$1") (pinfunction "P$1_P$1") (pintype "bidirectional"))
      (node (ref "U12") (pin "5") (pinfunction "P3.0/RXD_5") (pintype "bidirectional"))
    )
    (net (code "5") (name "/S1") (class "Default")
      (node (ref "FPC2") (pin "2") (pinfunction "2_2") (pintype "bidirectional"))
      (node (ref "U10") (pin "2") (pinfunction "S1_2") (pintype "bidirectional"))
    )
    (net (code "6") (name "/S2") (class "Default")
      (node (ref "FPC2") (pin "3") (pinfunction "3_3") (pintype "bidirectional"))
      (node (ref "U10") (pin "3") (pinfunction "S2_3") (pintype "bidirectional"))
    )
    (net (code "7") (name "/S3") (class "Default")
      (node (ref "FPC2") (pin "4") (pinfunction "4_4") (pintype "bidirectional"))
      (node (ref "U10") (pin "4") (pinfunction "S3_4") (pintype "bidirectional"))
    )
    (net (code "8") (name "/S4") (class "Default")
      (node (ref "FPC2") (pin "5") (pinfunction "5_5") (pintype "bidirectional"))
      (node (ref "U10") (pin "5") (pinfunction "S4_5") (pintype "bidirectional"))
    )
    (net (code "9") (name "/S5") (class "Default")
      (node (ref "FPC2") (pin "6") (pinfunction "6_6") (pintype "bidirectional"))
      (node (ref "U10") (pin "6") (pinfunction "S5_6") (pintype "bidirectional"))
    )
    (net (code "10") (name "/S6") (class "Default")
      (node (ref "FPC2") (pin "7") (pinfunction "7_7") (pintype "bidirectional"))
      (node (ref "U10") (pin "7") (pinfunction "S6_7") (pintype "bidirectional"))
    )
    (net (code "11") (name "/S7") (class "Default")
      (node (ref "FPC2") (pin "9") (pinfunction "9_9") (pintype "bidirectional"))
      (node (ref "U10") (pin "8") (pinfunction "S7_8") (pintype "bidirectional"))
    )
    (net (code "12") (name "/S8") (class "Default")
      (node (ref "FPC2") (pin "10") (pinfunction "10_10") (pintype "bidirectional"))
      (node (ref "U10") (pin "9") (pinfunction "S8_9") (pintype "bidirectional"))
    )
    (net (code "13") (name "/S9") (class "Default")
      (node (ref "FPC2") (pin "11") (pinfunction "11_11") (pintype "bidirectional"))
      (node (ref "U10") (pin "10") (pinfunction "S9_10") (pintype "bidirectional"))
    )
    (net (code "14") (name "/S10") (class "Default")
      (node (ref "FPC2") (pin "12") (pinfunction "12_12") (pintype "bidirectional"))
      (node (ref "U10") (pin "11") (pinfunction "S10_11") (pintype "bidirectional"))
    )
    (net (code "15") (name "/S11") (class "Default")
      (node (ref "FPC2") (pin "13") (pinfunction "13_13") (pintype "bidirectional"))
      (node (ref "U10") (pin "12") (pinfunction "S11_12") (pintype "bidirectional"))
    )
    (net (code "16") (name "/S12") (class "Default")
      (node (ref "FPC2") (pin "14") (pinfunction "14_14") (pintype "bidirectional"))
      (node (ref "U10") (pin "13") (pinfunction "S12_13") (pintype "bidirectional"))
    )
    (net (code "17") (name "/TXD_STC") (class "Default")
      (node (ref "P3") (pin "P$1") (pinfunction "P$1_P$1") (pintype "bidirectional"))
      (node (ref "U12") (pin "6") (pinfunction "P3.1/TXD_6") (pintype "bidirectional"))
    )
    (net (code "18") (name "/VOLN") (class "Default")
      (node (ref "C106") (pin "2") (pinfunction "2_2") (pintype "passive"))
      (node (ref "FB11") (pin "2") (pinfunction "2_2") (pintype "passive"))
      (node (ref "P55") (pin "P$1") (pinfunction "P$1_P$1") (pintype "bidirectional"))
    )
    (net (code "19") (name "/VOLP") (class "Default")
      (node (ref "C105") (pin "2") (pinfunction "2_2") (pintype "passive"))
      (node (ref "FB10") (pin "2") (pinfunction "2_2") (pintype "passive"))
      (node (ref "P54") (pin "P$1") (pinfunction "P$1_P$1") (pintype "bidirectional"))
    )
    (net (code "20") (name "3V3") (class "Default")
      (node (ref "C1") (pin "2") (pinfunction "2_2") (pintype "passive"))
      (node (ref "C14") (pin "2") (pinfunction "2_2") (pintype "passive"))
      (node (ref "C40") (pin "2") (pinfunction "2_2") (pintype "passive"))
      (node (ref "C42") (pin "2") (pinfunction "2_2") (pintype "passive"))
      (node (ref "C52") (pin "1") (pinfunction "1_1") (pintype "passive"))
      (node (ref "C53") (pin "1") (pinfunction "1_1") (pintype "passive"))
      (node (ref "FB1") (pin "1") (pinfunction "1_1") (pintype "passive"))
      (node (ref "FB17") (pin "2") (pinfunction "2_2") (pintype "passive"))
      (node (ref "L5") (pin "2") (pinfunction "2_2") (pintype "passive"))
      (node (ref "Q1") (pin "2") (pinfunction "S_2") (pintype "bidirectional"))
      (node (ref "Q10") (pin "2") (pinfunction "S_2") (pintype "passive"))
      (node (ref "R1") (pin "1") (pinfunction "1_1") (pintype "passive"))
      (node (ref "R15") (pin "1") (pinfunction "1_1") (pintype "passive"))
      (node (ref "R22") (pin "1") (pinfunction "1_1") (pintype "passive"))
      (node (ref "R57") (pin "2") (pinfunction "2_2") (pintype "passive"))
      (node (ref "R71") (pin "2") (pinfunction "2_2") (pintype "passive"))
      (node (ref "U7") (pin "P$3") (pinfunction "VDDIO_P$3") (pintype "bidirectional"))
      (node (ref "U7") (pin "P$7") (pinfunction "VDD_P$7") (pintype "bidirectional"))
    )
    (net (code "21") (name "AUDIO_EN") (class "Default")
      (node (ref "Q10") (pin "1") (pinfunction "G_1") (pintype "passive"))
      (node (ref "R71") (pin "1") (pinfunction "1_1") (pintype "passive"))
      (node (ref "U9") (pin "36") (pinfunction "SPICLK_N_36") (pintype "bidirectional"))
    )
    (net (code "22") (name "AUDIO_VDD") (class "Default")
      (node (ref "Q10") (pin "3") (pinfunction "D_3") (pintype "passive"))
      (node (ref "R139") (pin "2") (pinfunction "2_2") (pintype "passive"))
    )
    (net (code "23") (name "A_XBJ_POWER_OR_GND__GND_POWER") (class "Default")
      (node (ref "C1") (pin "1") (pinfunction "1_1") (pintype "passive"))
      (node (ref "C10") (pin "2") (pinfunction "2_2") (pintype "passive"))
      (node (ref "C102") (pin "2") (pinfunction "2_2") (pintype "passive"))
      (node (ref "C103") (pin "2") (pinfunction "2_2") (pintype "passive"))
      (node (ref "C104") (pin "2") (pinfunction "2_2") (pintype "passive"))
      (node (ref "C105") (pin "1") (pinfunction "1_1") (pintype "passive"))
      (node (ref "C106") (pin "1") (pinfunction "1_1") (pintype "passive"))
      (node (ref "C11") (pin "1") (pinfunction "1_1") (pintype "passive"))
      (node (ref "C12") (pin "1") (pinfunction "1_1") (pintype "passive"))
      (node (ref "C13") (pin "1") (pinfunction "1_1") (pintype "passive"))
      (node (ref "C14") (pin "1") (pinfunction "1_1") (pintype "passive"))
      (node (ref "C15") (pin "2") (pinfunction "2_2") (pintype "passive"))
      (node (ref "C16") (pin "1") (pinfunction "1_1") (pintype "passive"))
      (node (ref "C17") (pin "1") (pinfunction "1_1") (pintype "passive"))
      (node (ref "C18") (pin "1") (pinfunction "1_1") (pintype "passive"))
      (node (ref "C19") (pin "2") (pinfunction "2_2") (pintype "passive"))
      (node (ref "C2") (pin "1") (pinfunction "1_1") (pintype "passive"))
      (node (ref "C20") (pin "1") (pinfunction "1_1") (pintype "passive"))
      (node (ref "C21") (pin "1") (pinfunction "1_1") (pintype "passive"))
      (node (ref "C22") (pin "1") (pinfunction "1_1") (pintype "passive"))
      (node (ref "C23") (pin "2") (pinfunction "2_2") (pintype "passive"))
      (node (ref "C24") (pin "2") (pinfunction "2_2") (pintype "passive"))
      (node (ref "C25") (pin "1") (pinfunction "1_1") (pintype "passive"))
      (node (ref "C26") (pin "1") (pinfunction "1_1") (pintype "passive"))
      (node (ref "C27") (pin "1") (pinfunction "1_1") (pintype "passive"))
      (node (ref "C28") (pin "2") (pinfunction "2_2") (pintype "passive"))
      (node (ref "C29") (pin "1") (pinfunction "1_1") (pintype "passive"))
      (node (ref "C3") (pin "2") (pinfunction "2_2") (pintype "passive"))
      (node (ref "C30") (pin "2") (pinfunction "2_2") (pintype "passive"))
      (node (ref "C31") (pin "2") (pinfunction "2_2") (pintype "passive"))
      (node (ref "C32") (pin "2") (pinfunction "2_2") (pintype "passive"))
      (node (ref "C33") (pin "2") (pinfunction "2_2") (pintype "passive"))
      (node (ref "C34") (pin "1") (pinfunction "1_1") (pintype "passive"))
      (node (ref "C35") (pin "1") (pinfunction "1_1") (pintype "passive"))
      (node (ref "C36") (pin "1") (pinfunction "1_1") (pintype "passive"))
      (node (ref "C37") (pin "1") (pinfunction "1_1") (pintype "passive"))
      (node (ref "C38") (pin "1") (pinfunction "1_1") (pintype "passive"))
      (node (ref "C39") (pin "1") (pinfunction "1_1") (pintype "passive"))
      (node (ref "C4") (pin "2") (pinfunction "2_2") (pintype "passive"))
      (node (ref "C40") (pin "1") (pinfunction "1_1") (pintype "passive"))
      (node (ref "C5") (pin "1") (pinfunction "1_1") (pintype "passive"))
      (node (ref "C51") (pin "1") (pinfunction "1_1") (pintype "passive"))
      (node (ref "C52") (pin "2") (pinfunction "2_2") (pintype "passive"))
      (node (ref "C53") (pin "2") (pinfunction "2_2") (pintype "passive"))
      (node (ref "C6") (pin "1") (pinfunction "1_1") (pintype "passive"))
      (node (ref "C64") (pin "1") (pinfunction "1_1") (pintype "passive"))
      (node (ref "C66") (pin "1") (pinfunction "1_1") (pintype "passive"))
      (node (ref "C67") (pin "2") (pinfunction "2_2") (pintype "passive"))
      (node (ref "C7") (pin "2") (pinfunction "2_2") (pintype "passive"))
      (node (ref "C8") (pin "2") (pinfunction "2_2") (pintype "passive"))
      (node (ref "C9") (pin "2") (pinfunction "2_2") (pintype "passive"))
      (node (ref "D1") (pin "1") (pinfunction "1_1") (pintype "bidirectional"))
      (node (ref "D3") (pin "1") (pinfunction "1_1") (pintype "bidirectional"))
      (node (ref "D4") (pin "1") (pinfunction "1_1") (pintype "bidirectional"))
      (node (ref "FPC2") (pin "1") (pinfunction "1_1") (pintype "bidirectional"))
      (node (ref "FPC2") (pin "15") (pinfunction "15_15") (pintype "bidirectional"))
      (node (ref "FPC2") (pin "16") (pinfunction "16_16") (pintype "bidirectional"))
      (node (ref "FPC2") (pin "17") (pinfunction "17_17") (pintype "bidirectional"))
      (node (ref "FPC3") (pin "14") (pinfunction "14_14") (pintype "bidirectional"))
      (node (ref "FPC3") (pin "16") (pinfunction "16_16") (pintype "bidirectional"))
      (node (ref "FPC3") (pin "17") (pinfunction "17_17") (pintype "bidirectional"))
      (node (ref "FPC3") (pin "3") (pinfunction "3_3") (pintype "bidirectional"))
      (node (ref "FPC3") (pin "4") (pinfunction "4_4") (pintype "bidirectional"))
      (node (ref "J2") (pin "1") (pinfunction "1_1") (pintype "passive"))
      (node (ref "J3") (pin "A1") (pinfunction "GND_A1") (pintype "bidirectional"))
      (node (ref "J3") (pin "A12") (pinfunction "GND_A12") (pintype "bidirectional"))
      (node (ref "J3") (pin "B1") (pinfunction "GND_B1") (pintype "bidirectional"))
      (node (ref "J3") (pin "B12") (pinfunction "GND_B12") (pintype "bidirectional"))
      (node (ref "J3") (pin "P$1") (pinfunction "P$17_P$1") (pintype "bidirectional"))
      (node (ref "J3") (pin "P$2") (pinfunction "P$18_P$2") (pintype "bidirectional"))
      (node (ref "J3") (pin "P$3") (pinfunction "P$19_P$3") (pintype "bidirectional"))
      (node (ref "J3") (pin "P$4") (pinfunction "P$20_P$4") (pintype "bidirectional"))
      (node (ref "J4") (pin "1") (pinfunction "1_1") (pintype "passive"))
      (node (ref "J5") (pin "1") (pinfunction "1_1") (pintype "passive"))
      (node (ref "J6") (pin "1") (pinfunction "1_1") (pintype "passive"))
      (node (ref "J7") (pin "1") (pinfunction "1_1") (pintype "bidirectional"))
      (node (ref "J7") (pin "3") (pinfunction "3_3") (pintype "bidirectional"))
      (node (ref "J7") (pin "4") (pinfunction "4_4") (pintype "bidirectional"))
      (node (ref "LED1") (pin "-") (pinfunction "-_-") (pintype "passive"))
      (node (ref "MIC3") (pin "4") (pinfunction "GND0_4") (pintype "power_in"))
      (node (ref "MIC3") (pin "6") (pinfunction "GND1_6") (pintype "power_in"))
      (node (ref "P16") (pin "P$1") (pinfunction "P$1_P$1") (pintype "bidirectional"))
      (node (ref "P5") (pin "P$1") (pinfunction "P$1_P$1") (pintype "bidirectional"))
      (node (ref "P6") (pin "P$1") (pinfunction "P$1_P$1") (pintype "bidirectional"))
      (node (ref "P8") (pin "1") (pinfunction "1_1") (pintype "bidirectional"))
      (node (ref "Q4") (pin "P$2") (pinfunction "P$2_P$2") (pintype "bidirectional"))
      (node (ref "Q6") (pin "P$2") (pinfunction "P$2_P$2") (pintype "bidirectional"))
      (node (ref "R143") (pin "1") (pinfunction "1_1") (pintype "passive"))
      (node (ref "R17") (pin "2") (pinfunction "2_2") (pintype "passive"))
      (node (ref "R171") (pin "2") (pinfunction "2_2") (pintype "passive"))
      (node (ref "R19") (pin "1") (pinfunction "1_1") (pintype "passive"))
      (node (ref "R20") (pin "2") (pinfunction "2_2") (pintype "passive"))
      (node (ref "R28") (pin "2") (pinfunction "2_2") (pintype "passive"))
      (node (ref "R3") (pin "1") (pinfunction "1_1") (pintype "passive"))
      (node (ref "R32") (pin "2") (pinfunction "2_2") (pintype "passive"))
      (node (ref "R33") (pin "1") (pinfunction "1_1") (pintype "passive"))
      (node (ref "R36") (pin "2") (pinfunction "2_2") (pintype "passive"))
      (node (ref "R38") (pin "1") (pinfunction "1_1") (pintype "passive"))
      (node (ref "R40") (pin "1") (pinfunction "1_1") (pintype "passive"))
      (node (ref "R75") (pin "1") (pinfunction "1_1") (pintype "passive"))
      (node (ref "SW1") (pin "1") (pinfunction "1_1") (pintype "bidirectional"))
      (node (ref "SW1") (pin "2") (pinfunction "2_2") (pintype "bidirectional"))
      (node (ref "SW1") (pin "3") (pinfunction "3_3") (pintype "bidirectional"))
      (node (ref "SW1") (pin "4") (pinfunction "4_4") (pintype "bidirectional"))
      (node (ref "SW1") (pin "A1") (pinfunction "A1_A1") (pintype "bidirectional"))
      (node (ref "SW1") (pin "A2") (pinfunction "A2_A2") (pintype "bidirectional"))
      (node (ref "SW2") (pin "1") (pinfunction "1_1") (pintype "bidirectional"))
      (node (ref "SW2") (pin "2") (pinfunction "2_2") (pintype "bidirectional"))
      (node (ref "SW2") (pin "3") (pinfunction "3_3") (pintype "bidirectional"))
      (node (ref "SW2") (pin "4") (pinfunction "4_4") (pintype "bidirectional"))
      (node (ref "SW2") (pin "A1") (pinfunction "A1_A1") (pintype "bidirectional"))
      (node (ref "SW2") (pin "A2") (pinfunction "A2_A2") (pintype "bidirectional"))
      (node (ref "SW3") (pin "1") (pinfunction "1_1") (pintype "bidirectional"))
      (node (ref "SW3") (pin "2") (pinfunction "2_2") (pintype "bidirectional"))
      (node (ref "SW3") (pin "3") (pinfunction "3_3") (pintype "bidirectional"))
      (node (ref "SW3") (pin "4") (pinfunction "4_4") (pintype "bidirectional"))
      (node (ref "SW3") (pin "A1") (pinfunction "A1_A1") (pintype "bidirectional"))
      (node (ref "SW3") (pin "A2") (pinfunction "A2_A2") (pintype "bidirectional"))
      (node (ref "U1") (pin "P$4") (pinfunction "VSS_P$4") (pintype "bidirectional"))
      (node (ref "U10") (pin "21") (pinfunction "GND_21") (pintype "bidirectional"))
      (node (ref "U11") (pin "7") (pinfunction "GND_7") (pintype "bidirectional"))
      (node (ref "U11") (pin "9") (pinfunction "PE_9") (pintype "bidirectional"))
      (node (ref "U12") (pin "4") (pinfunction "GND_4") (pintype "bidirectional"))
      (node (ref "U12") (pin "P$9") (pinfunction "GND9_P$9") (pintype "bidirectional"))
      (node (ref "U13") (pin "2") (pinfunction "GND_2") (pintype "power_in"))
      (node (ref "U3") (pin "3") (pinfunction "GND_3") (pintype "bidirectional"))
      (node (ref "U3") (pin "EP") (pinfunction "EP_EP") (pintype "bidirectional"))
      (node (ref "U5") (pin "P$2") (pinfunction "GND_P$2") (pintype "bidirectional"))
      (node (ref "U55") (pin "1") (pinfunction "1_1") (pintype "bidirectional"))
      (node (ref "U55") (pin "2") (pinfunction "2_2") (pintype "bidirectional"))
      (node (ref "U55") (pin "3") (pinfunction "3_3") (pintype "bidirectional"))
      (node (ref "U55") (pin "COM") (pinfunction "COM_COM") (pintype "bidirectional"))
      (node (ref "U55") (pin "E") (pinfunction "E_E") (pintype "bidirectional"))
      (node (ref "U6") (pin "P$3") (pinfunction "GND_P$3") (pintype "bidirectional"))
      (node (ref "U6") (pin "P$9") (pinfunction "EP_P$9") (pintype "bidirectional"))
      (node (ref "U7") (pin "P$4") (pinfunction "NC1_P$4") (pintype "bidirectional"))
      (node (ref "U7") (pin "P$8") (pinfunction "GNDIO_P$8") (pintype "bidirectional"))
      (node (ref "U7") (pin "P$9") (pinfunction "GND_P$9") (pintype "bidirectional"))
      (node (ref "U8") (pin "4") (pinfunction "GND_4") (pintype "bidirectional"))
      (node (ref "U9") (pin "57") (pinfunction "EP_57") (pintype "bidirectional"))
      (node (ref "X1") (pin "2") (pinfunction "G2_2") (pintype "power_in"))
      (node (ref "X1") (pin "4") (pinfunction "G1_4") (pintype "power_in"))
    )
    (net (code "24") (name "BAT+") (class "Default")
      (node (ref "C67") (pin "1") (pinfunction "1_1") (pintype "passive"))
      (node (ref "J7") (pin "2") (pinfunction "2_2") (pintype "bidirectional"))
      (node (ref "Q5") (pin "3") (pinfunction "D_3") (pintype "bidirectional"))
      (node (ref "R30") (pin "2") (pinfunction "2_2") (pintype "passive"))
      (node (ref "U6") (pin "P$5") (pinfunction "BAT_P$5") (pintype "bidirectional"))
    )
    (net (code "25") (name "BAT_ADC") (class "Default")
      (node (ref "C26") (pin "2") (pinfunction "2_2") (pintype "passive"))
      (node (ref "R30") (pin "1") (pinfunction "1_1") (pintype "passive"))
      (node (ref "R36") (pin "1") (pinfunction "1_1") (pintype "passive"))
      (node (ref "U9") (pin "6") (pinfunction "GPIO1_6") (pintype "bidirectional"))
    )
    (net (code "26") (name "BL_EN") (class "Default")
      (node (ref "R76") (pin "2") (pinfunction "2_2") (pintype "passive"))
      (node (ref "U9") (pin "18") (pinfunction "GPIO13_18") (pintype "bidirectional"))
    )
    (net (code "27") (name "CHRG") (class "Default")
      (node (ref "R34") (pin "2") (pinfunction "2_2") (pintype "passive"))
      (node (ref "U9") (pin "21") (pinfunction "XTAL_32K_P_21") (pintype "bidirectional"))
    )
    (net (code "28") (name "CHRG_1") (class "Default")
      (node (ref "R28") (pin "1") (pinfunction "1_1") (pintype "passive"))
      (node (ref "R34") (pin "1") (pinfunction "1_1") (pintype "passive"))
      (node (ref "R5") (pin "2") (pinfunction "2_2") (pintype "passive"))
      (node (ref "U6") (pin "P$7") (pinfunction "CHRG_P$7") (pintype "bidirectional"))
    )
    (net (code "29") (name "DISPLAY_EN") (class "Default")
      (node (ref "R56") (pin "2") (pinfunction "2_2") (pintype "passive"))
      (node (ref "U9") (pin "45") (pinfunction "MTDO_45") (pintype "bidirectional"))
    )
    (net (code "30") (name "DISPLAY_VDD") (class "Default")
      (node (ref "C22") (pin "2") (pinfunction "2_2") (pintype "passive"))
      (node (ref "C25") (pin "2") (pinfunction "2_2") (pintype "passive"))
      (node (ref "C27") (pin "2") (pinfunction "2_2") (pintype "passive"))
      (node (ref "FPC3") (pin "5") (pinfunction "5_5") (pintype "bidirectional"))
      (node (ref "FPC3") (pin "6") (pinfunction "6_6") (pintype "bidirectional"))
      (node (ref "FPC3") (pin "7") (pinfunction "7_7") (pintype "bidirectional"))
      (node (ref "Q1") (pin "3") (pinfunction "D_3") (pintype "bidirectional"))
      (node (ref "R74") (pin "2") (pinfunction "2_2") (pintype "passive"))
    )
    (net (code "31") (name "DONE_1") (class "Default")
      (node (ref "U6") (pin "P$6") (pinfunction "DONE_P$6") (pintype "bidirectional"))
    )
    (net (code "32") (name "DTR") (class "Default")
      (node (ref "R12") (pin "2") (pinfunction "2_2") (pintype "passive"))
      (node (ref "U3") (pin "4") (pinfunction "DTR#_4") (pintype "bidirectional"))
      (node (ref "U4") (pin "4") (pinfunction "E2_4") (pintype "bidirectional"))
    )
    (net (code "33") (name "EC04_A") (class "Default")
      (node (ref "C64") (pin "2") (pinfunction "2_2") (pintype "passive"))
      (node (ref "R62") (pin "2") (pinfunction "2_2") (pintype "passive"))
      (node (ref "U55") (pin "A") (pinfunction "A_A") (pintype "bidirectional"))
      (node (ref "U9") (pin "26") (pinfunction "GPIO20_26") (pintype "bidirectional"))
    )
    (net (code "34") (name "EC04_B") (class "Default")
      (node (ref "C5") (pin "2") (pinfunction "2_2") (pintype "passive"))
      (node (ref "R6") (pin "2") (pinfunction "2_2") (pintype "passive"))
      (node (ref "U55") (pin "B") (pinfunction "B_B") (pintype "bidirectional"))
      (node (ref "U9") (pin "25") (pinfunction "GPIO19_25") (pintype "bidirectional"))
    )
    (net (code "35") (name "ESP32_EN") (class "Default")
      (node (ref "C17") (pin "2") (pinfunction "2_2") (pintype "passive"))
      (node (ref "R14") (pin "2") (pinfunction "2_2") (pintype "passive"))
      (node (ref "SW1") (pin "B") (pinfunction "B_B") (pintype "bidirectional"))
      (node (ref "U4") (pin "6") (pinfunction "C1_6") (pintype "bidirectional"))
      (node (ref "U9") (pin "4") (pinfunction "CHIP_PU_4") (pintype "bidirectional"))
    )
    (net (code "36") (name "ESP_POWER_CTL") (class "Default")
      (node (ref "R27") (pin "2") (pinfunction "2_2") (pintype "passive"))
      (node (ref "U12") (pin "3") (pinfunction "P5.5/SS_3") (pintype "bidirectional"))
    )
    (net (code "37") (name "E_BUTTON") (class "Default")
      (node (ref "C66") (pin "2") (pinfunction "2_2") (pintype "passive"))
      (node (ref "R63") (pin "2") (pinfunction "2_2") (pintype "passive"))
      (node (ref "U55") (pin "D") (pinfunction "D_D") (pintype "bidirectional"))
      (node (ref "U9") (pin "24") (pinfunction "GPIO18_24") (pintype "bidirectional"))
    )
    (net (code "38") (name "I2SOUT_LRCK") (class "Default")
      (node (ref "U11") (pin "2") (pinfunction "LRCLK_2") (pintype "bidirectional"))
      (node (ref "U9") (pin "52") (pinfunction "GPIO46_52") (pintype "bidirectional"))
    )
    (net (code "39") (name "I2SOUT_SCLK") (class "Default")
      (node (ref "U11") (pin "3") (pinfunction "BCLK_3") (pintype "bidirectional"))
      (node (ref "U9") (pin "48") (pinfunction "MTMS_48") (pintype "bidirectional"))
    )
    (net (code "40") (name "I2SOUT_SD") (class "Default")
      (node (ref "U11") (pin "4") (pinfunction "SDATA_4") (pintype "bidirectional"))
      (node (ref "U9") (pin "47") (pinfunction "MTDI_47") (pintype "bidirectional"))
    )
    (net (code "41") (name "IO0_BOOT") (class "Default")
      (node (ref "C21") (pin "2") (pinfunction "2_2") (pintype "passive"))
      (node (ref "R65") (pin "2") (pinfunction "2_2") (pintype "passive"))
      (node (ref "SW2") (pin "B") (pinfunction "B_B") (pintype "bidirectional"))
      (node (ref "U4") (pin "3") (pinfunction "C2_3") (pintype "bidirectional"))
      (node (ref "U9") (pin "5") (pinfunction "GPIO0_5") (pintype "bidirectional"))
    )
    (net (code "42") (name "IO9_LCD_D{slash}C") (class "Default")
      (node (ref "FPC3") (pin "11") (pinfunction "11_11") (pintype "bidirectional"))
      (node (ref "U9") (pin "15") (pinfunction "GPIO10_15") (pintype "bidirectional"))
    )
    (net (code "43") (name "IO10_LCD_CS") (class "Default")
      (node (ref "FPC3") (pin "9") (pinfunction "9_9") (pintype "bidirectional"))
      (node (ref "U9") (pin "14") (pinfunction "GPIO9_14") (pintype "bidirectional"))
    )
    (net (code "44") (name "IO13_LCD_MOSI") (class "Default")
      (node (ref "FPC3") (pin "12") (pinfunction "12_12") (pintype "bidirectional"))
      (node (ref "U9") (pin "13") (pinfunction "GPIO8_13") (pintype "bidirectional"))
    )
    (net (code "45") (name "IO14_LCD_SCK") (class "Default")
      (node (ref "FPC3") (pin "10") (pinfunction "10_10") (pintype "bidirectional"))
      (node (ref "U9") (pin "12") (pinfunction "GPIO7_12") (pintype "bidirectional"))
    )
    (net (code "46") (name "LCD_POWER_DET") (class "Default")
      (node (ref "R7") (pin "2") (pinfunction "2_2") (pintype "passive"))
      (node (ref "U9") (pin "19") (pinfunction "GPIO14_19") (pintype "bidirectional"))
    )
    (net (code "47") (name "LCD_RESET") (class "Default")
      (node (ref "FPC3") (pin "8") (pinfunction "8_8") (pintype "bidirectional"))
      (node (ref "U9") (pin "11") (pinfunction "GPIO6_11") (pintype "bidirectional"))
    )
    (net (code "48") (name "LED") (class "Default")
      (node (ref "R42") (pin "2") (pinfunction "2_2") (pintype "passive"))
      (node (ref "U9") (pin "22") (pinfunction "XTAL_32K_N_22") (pintype "bidirectional"))
    )
    (net (code "49") (name "LEDK") (class "Default")
      (node (ref "FPC3") (pin "15") (pinfunction "15_15") (pintype "bidirectional"))
      (node (ref "Q6") (pin "P$3") (pinfunction "P$3_P$3") (pintype "bidirectional"))
    )
    (net (code "50") (name "MIC_MCLK") (class "Default")
      (node (ref "R43") (pin "2") (pinfunction "2_2") (pintype "passive"))
      (node (ref "U9") (pin "17") (pinfunction "GPIO12_17") (pintype "bidirectional"))
    )
    (net (code "51") (name "MIC_SD2") (class "Default")
      (node (ref "R44") (pin "1") (pinfunction "1_1") (pintype "passive"))
      (node (ref "U9") (pin "16") (pinfunction "GPIO11_16") (pintype "bidirectional"))
    )
    (net (code "52") (name "MIC_VDD_3V3") (class "Default")
      (node (ref "C32") (pin "1") (pinfunction "1_1") (pintype "passive"))
      (node (ref "C33") (pin "1") (pinfunction "1_1") (pintype "passive"))
      (node (ref "FB1") (pin "2") (pinfunction "2_2") (pintype "passive"))
      (node (ref "MIC3") (pin "1") (pinfunction "VDD_1") (pintype "power_in"))
    )
    (net (code "53") (name "Net-(ANT1-PadP$1)") (class "Default")
      (node (ref "ANT1") (pin "P$1") (pinfunction "P$1_P$1") (pintype "bidirectional"))
      (node (ref "L2") (pin "2") (pinfunction "2_2") (pintype "passive"))
    )
    (net (code "54") (name "Net-(C2-Pad2)") (class "Default")
      (node (ref "C2") (pin "2") (pinfunction "2_2") (pintype "passive"))
      (node (ref "D007") (pin "C") (pinfunction "C_C") (pintype "passive"))
      (node (ref "J1") (pin "P$1") (pinfunction "P$1_P$1") (pintype "bidirectional"))
      (node (ref "R1") (pin "2") (pinfunction "2_2") (pintype "passive"))
    )
    (net (code "55") (name "Net-(C4-Pad1)") (class "Default")
      (node (ref "C4") (pin "1") (pinfunction "1_1") (pintype "passive"))
      (node (ref "L1") (pin "2") (pinfunction "2_2") (pintype "passive"))
      (node (ref "L2") (pin "1") (pinfunction "1_1") (pintype "passive"))
    )
    (net (code "56") (name "Net-(D007-PadA)") (class "Default")
      (node (ref "D007") (pin "A") (pinfunction "A_A") (pintype "passive"))
      (node (ref "J1") (pin "P$2") (pinfunction "P$2_P$2") (pintype "bidirectional"))
      (node (ref "Q4") (pin "P$3") (pinfunction "P$3_P$3") (pintype "bidirectional"))
    )
    (net (code "57") (name "Net-(FPC3-Pad13)") (class "Default")
      (node (ref "FPC3") (pin "13") (pinfunction "13_13") (pintype "bidirectional"))
      (node (ref "R70") (pin "2") (pinfunction "2_2") (pintype "passive"))
    )
    (net (code "58") (name "Net-(J3-CC1)") (class "Default")
      (node (ref "J3") (pin "A5") (pinfunction "CC1_A5") (pintype "bidirectional"))
      (node (ref "R20") (pin "1") (pinfunction "1_1") (pintype "passive"))
    )
    (net (code "59") (name "Net-(J3-CC2)") (class "Default")
      (node (ref "J3") (pin "B5") (pinfunction "CC2_B5") (pintype "bidirectional"))
      (node (ref "R19") (pin "2") (pinfunction "2_2") (pintype "passive"))
    )
    (net (code "60") (name "Net-(LED1-Pad+)") (class "Default")
      (node (ref "LED1") (pin "+") (pinfunction "+_+") (pintype "passive"))
      (node (ref "R42") (pin "1") (pinfunction "1_1") (pintype "passive"))
    )
    (net (code "61") (name "Net-(MIC3-CLK)") (class "Default")
      (node (ref "MIC3") (pin "2") (pinfunction "CLK_2") (pintype "input"))
      (node (ref "R43") (pin "1") (pinfunction "1_1") (pintype "passive"))
    )
    (net (code "62") (name "Net-(MIC3-DATA)") (class "Default")
      (node (ref "MIC3") (pin "3") (pinfunction "DATA_3") (pintype "output"))
      (node (ref "R44") (pin "2") (pinfunction "2_2") (pintype "passive"))
    )
    (net (code "63") (name "Net-(MIC3-L{slash}R)") (class "Default")
      (node (ref "MIC3") (pin "5") (pinfunction "L/R_5") (pintype "input"))
      (node (ref "R171") (pin "1") (pinfunction "1_1") (pintype "passive"))
    )
    (net (code "64") (name "Net-(P7-Pad1)") (class "Default")
      (node (ref "P7") (pin "1") (pinfunction "1_1") (pintype "bidirectional"))
      (node (ref "R31") (pin "2") (pinfunction "2_2") (pintype "passive"))
      (node (ref "R33") (pin "2") (pinfunction "2_2") (pintype "passive"))
    )
    (net (code "65") (name "Net-(Q1-G)") (class "Default")
      (node (ref "Q1") (pin "1") (pinfunction "G_1") (pintype "bidirectional"))
      (node (ref "R56") (pin "1") (pinfunction "1_1") (pintype "passive"))
      (node (ref "R57") (pin "1") (pinfunction "1_1") (pintype "passive"))
    )
    (net (code "66") (name "Net-(Q4-PadP$1)") (class "Default")
      (node (ref "Q4") (pin "P$1") (pinfunction "P$1_P$1") (pintype "bidirectional"))
      (node (ref "R2") (pin "2") (pinfunction "2_2") (pintype "passive"))
      (node (ref "R3") (pin "2") (pinfunction "2_2") (pintype "passive"))
    )
    (net (code "67") (name "Net-(Q5-G)") (class "Default")
      (node (ref "Q5") (pin "1") (pinfunction "G_1") (pintype "bidirectional"))
      (node (ref "R37") (pin "1") (pinfunction "1_1") (pintype "passive"))
      (node (ref "R38") (pin "2") (pinfunction "2_2") (pintype "passive"))
    )
    (net (code "68") (name "Net-(Q6-PadP$1)") (class "Default")
      (node (ref "Q6") (pin "P$1") (pinfunction "P$1_P$1") (pintype "bidirectional"))
      (node (ref "R75") (pin "2") (pinfunction "2_2") (pintype "passive"))
      (node (ref "R76") (pin "1") (pinfunction "1_1") (pintype "passive"))
    )
    (net (code "69") (name "Net-(Q7-G)") (class "Default")
      (node (ref "Q7") (pin "1") (pinfunction "G_1") (pintype "passive"))
      (node (ref "R27") (pin "1") (pinfunction "1_1") (pintype "passive"))
      (node (ref "R9") (pin "2") (pinfunction "2_2") (pintype "passive"))
    )
    (net (code "70") (name "Net-(U1-OSCI)") (class "Default")
      (node (ref "C7") (pin "1") (pinfunction "1_1") (pintype "passive"))
      (node (ref "U1") (pin "P$1") (pinfunction "OSCI_P$1") (pintype "bidirectional"))
      (node (ref "Y3") (pin "2") (pinfunction "2_2") (pintype "passive"))
    )
    (net (code "71") (name "Net-(U1-OSCO)") (class "Default")
      (node (ref "C8") (pin "1") (pinfunction "1_1") (pintype "passive"))
      (node (ref "U1") (pin "P$2") (pinfunction "OSCO_P$2") (pintype "bidirectional"))
      (node (ref "Y3") (pin "1") (pinfunction "1_1") (pintype "passive"))
    )
    (net (code "72") (name "Net-(U1-SCL)") (class "Default")
      (node (ref "R16") (pin "2") (pinfunction "2_2") (pintype "passive"))
      (node (ref "U1") (pin "P$6") (pinfunction "SCL_P$6") (pintype "bidirectional"))
    )
    (net (code "73") (name "Net-(U1-SDA)") (class "Default")
      (node (ref "R21") (pin "2") (pinfunction "2_2") (pintype "passive"))
      (node (ref "U1") (pin "P$5") (pinfunction "SDA_P$5") (pintype "bidirectional"))
    )
    (net (code "74") (name "Net-(U3-RXD)") (class "Default")
      (node (ref "R10") (pin "2") (pinfunction "2_2") (pintype "passive"))
      (node (ref "U3") (pin "9") (pinfunction "RXD_9") (pintype "bidirectional"))
    )
    (net (code "75") (name "Net-(U3-TXD)") (class "Default")
      (node (ref "R11") (pin "2") (pinfunction "2_2") (pintype "passive"))
      (node (ref "U3") (pin "8") (pinfunction "TXD_8") (pintype "bidirectional"))
    )
    (net (code "76") (name "Net-(U3-V3)") (class "Default")
      (node (ref "C10") (pin "1") (pinfunction "1_1") (pintype "passive"))
      (node (ref "U3") (pin "10") (pinfunction "V3_10") (pintype "bidirectional"))
    )
    (net (code "77") (name "Net-(U4-B1)") (class "Default")
      (node (ref "R12") (pin "1") (pinfunction "1_1") (pintype "passive"))
      (node (ref "U4") (pin "2") (pinfunction "B1_2") (pintype "input"))
    )
    (net (code "78") (name "Net-(U4-B2)") (class "Default")
      (node (ref "R13") (pin "1") (pinfunction "1_1") (pintype "passive"))
      (node (ref "U4") (pin "5") (pinfunction "B2_5") (pintype "input"))
    )
    (net (code "79") (name "Net-(U6-PROG)") (class "Default")
      (node (ref "R32") (pin "1") (pinfunction "1_1") (pintype "passive"))
      (node (ref "U6") (pin "P$2") (pinfunction "PROG_P$2") (pintype "bidirectional"))
    )
    (net (code "80") (name "Net-(U6-TEMP)") (class "Default")
      (node (ref "R31") (pin "1") (pinfunction "1_1") (pintype "passive"))
      (node (ref "R48") (pin "2") (pinfunction "2_2") (pintype "passive"))
      (node (ref "U6") (pin "P$1") (pinfunction "TEMP_P$1") (pintype "bidirectional"))
    )
    (net (code "81") (name "Net-(U7-CS)") (class "Default")
      (node (ref "R22") (pin "2") (pinfunction "2_2") (pintype "passive"))
      (node (ref "U7") (pin "P$10") (pinfunction "CS_P$10") (pintype "bidirectional"))
    )
    (net (code "82") (name "Net-(U7-SCX)") (class "Default")
      (node (ref "R24") (pin "2") (pinfunction "2_2") (pintype "passive"))
      (node (ref "U7") (pin "P$12") (pinfunction "SCX_P$12") (pintype "bidirectional"))
    )
    (net (code "83") (name "Net-(U7-SDX)") (class "Default")
      (node (ref "R25") (pin "2") (pinfunction "2_2") (pintype "passive"))
      (node (ref "U7") (pin "P$2") (pinfunction "SDX_P$2") (pintype "bidirectional"))
    )
    (net (code "84") (name "Net-(U9-LNA_IN)") (class "Default")
      (node (ref "C3") (pin "1") (pinfunction "1_1") (pintype "passive"))
      (node (ref "L1") (pin "1") (pinfunction "1_1") (pintype "passive"))
      (node (ref "U9") (pin "1") (pinfunction "LNA_IN_1") (pintype "bidirectional"))
    )
    (net (code "85") (name "Net-(U9-VDD3P3_1)") (class "Default")
      (node (ref "C15") (pin "1") (pinfunction "1_1") (pintype "passive"))
      (node (ref "C16") (pin "2") (pinfunction "2_2") (pintype "passive"))
      (node (ref "L4") (pin "1") (pinfunction "1_1") (pintype "passive"))
      (node (ref "U9") (pin "2") (pinfunction "VDD3P3_1_2") (pintype "bidirectional"))
      (node (ref "U9") (pin "3") (pinfunction "VDD3P3_2_3") (pintype "bidirectional"))
    )
    (net (code "86") (name "Net-(U9-XTAL_N)") (class "Default")
      (node (ref "C12") (pin "2") (pinfunction "2_2") (pintype "passive"))
      (node (ref "U9") (pin "53") (pinfunction "XTAL_N_53") (pintype "bidirectional"))
      (node (ref "X1") (pin "3") (pinfunction "X2_3") (pintype "bidirectional"))
    )
    (net (code "87") (name "Net-(U9-XTAL_P)") (class "Default")
      (node (ref "L3") (pin "2") (pinfunction "2_2") (pintype "passive"))
      (node (ref "U9") (pin "54") (pinfunction "XTAL_P_54") (pintype "bidirectional"))
    )
    (net (code "88") (name "Net-(U10-INT)") (class "Default")
      (node (ref "R66") (pin "2") (pinfunction "2_2") (pintype "passive"))
      (node (ref "U10") (pin "20") (pinfunction "INT_20") (pintype "bidirectional"))
    )
    (net (code "89") (name "Net-(U10-IOCAP)") (class "Default")
      (node (ref "C29") (pin "2") (pinfunction "2_2") (pintype "passive"))
      (node (ref "U10") (pin "1") (pinfunction "IOCAP_1") (pintype "bidirectional"))
    )
    (net (code "90") (name "Net-(U10-RESX)") (class "Default")
      (node (ref "R79") (pin "2") (pinfunction "2_2") (pintype "passive"))
      (node (ref "U10") (pin "17") (pinfunction "RESX_17") (pintype "bidirectional"))
    )
    (net (code "91") (name "Net-(U10-SCL)") (class "Default")
      (node (ref "R78") (pin "2") (pinfunction "2_2") (pintype "passive"))
      (node (ref "U10") (pin "18") (pinfunction "SCL_18") (pintype "bidirectional"))
    )
    (net (code "92") (name "Net-(U10-SDA)") (class "Default")
      (node (ref "R77") (pin "2") (pinfunction "2_2") (pintype "passive"))
      (node (ref "U10") (pin "19") (pinfunction "SDA_19") (pintype "bidirectional"))
    )
    (net (code "93") (name "Net-(U10-VCAP)") (class "Default")
      (node (ref "C30") (pin "1") (pinfunction "1_1") (pintype "passive"))
      (node (ref "U10") (pin "15") (pinfunction "VCAP_15") (pintype "bidirectional"))
    )
    (net (code "94") (name "Net-(U11-CTRL)") (class "Default")
      (node (ref "R139") (pin "1") (pinfunction "1_1") (pintype "passive"))
      (node (ref "R143") (pin "2") (pinfunction "2_2") (pintype "passive"))
      (node (ref "U11") (pin "1") (pinfunction "CTRL_1") (pintype "bidirectional"))
    )
    (net (code "95") (name "Net-(U11-VDD)") (class "Default")
      (node (ref "C102") (pin "1") (pinfunction "1_1") (pintype "passive"))
      (node (ref "C103") (pin "1") (pinfunction "1_1") (pintype "passive"))
      (node (ref "C104") (pin "1") (pinfunction "1_1") (pintype "passive"))
      (node (ref "FB17") (pin "1") (pinfunction "1_1") (pintype "passive"))
      (node (ref "U11") (pin "6") (pinfunction "VDD_6") (pintype "bidirectional"))
    )
    (net (code "96") (name "Net-(U11-VON)") (class "Default")
      (node (ref "FB11") (pin "1") (pinfunction "1_1") (pintype "passive"))
      (node (ref "U11") (pin "5") (pinfunction "VON_5") (pintype "bidirectional"))
    )
    (net (code "97") (name "Net-(U11-VOP)") (class "Default")
      (node (ref "FB10") (pin "1") (pinfunction "1_1") (pintype "passive"))
      (node (ref "U11") (pin "8") (pinfunction "VOP_8") (pintype "bidirectional"))
    )
    (net (code "98") (name "Net-(U12-P5.4{slash}MOSI)") (class "Default")
      (node (ref "R7") (pin "1") (pinfunction "1_1") (pintype "passive"))
      (node (ref "U12") (pin "1") (pinfunction "P5.4/MOSI_1") (pintype "bidirectional"))
    )
    (net (code "99") (name "Net-(U13-EN)") (class "Default")
      (node (ref "R4") (pin "2") (pinfunction "2_2") (pintype "passive"))
      (node (ref "U13") (pin "1") (pinfunction "EN_1") (pintype "input"))
    )
    (net (code "100") (name "Net-(U13-FB)") (class "Default")
      (node (ref "C42") (pin "1") (pinfunction "1_1") (pintype "passive"))
      (node (ref "R15") (pin "2") (pinfunction "2_2") (pintype "passive"))
      (node (ref "R17") (pin "1") (pinfunction "1_1") (pintype "passive"))
      (node (ref "U13") (pin "5") (pinfunction "FB_5") (pintype "input"))
    )
    (net (code "101") (name "Net-(U13-SW)") (class "Default")
      (node (ref "L5") (pin "1") (pinfunction "1_1") (pintype "passive"))
      (node (ref "U13") (pin "3") (pinfunction "SW_3") (pintype "bidirectional"))
    )
    (net (code "102") (name "Net-(X1-X1)") (class "Default")
      (node (ref "C11") (pin "2") (pinfunction "2_2") (pintype "passive"))
      (node (ref "L3") (pin "1") (pinfunction "1_1") (pintype "passive"))
      (node (ref "X1") (pin "1") (pinfunction "X1_1") (pintype "bidirectional"))
    )
    (net (code "103") (name "POWER_CTL") (class "Default")
      (node (ref "R4") (pin "1") (pinfunction "1_1") (pintype "passive"))
      (node (ref "U9") (pin "37") (pinfunction "SPICLK_P_37") (pintype "bidirectional"))
    )
    (net (code "104") (name "POWER_KEY") (class "Default")
      (node (ref "C36") (pin "2") (pinfunction "2_2") (pintype "passive"))
      (node (ref "R601") (pin "1") (pinfunction "1_1") (pintype "passive"))
      (node (ref "SW3") (pin "B") (pinfunction "B_B") (pintype "bidirectional"))
      (node (ref "U12") (pin "8") (pinfunction "P3.3/MISO_8") (pintype "bidirectional"))
    )
    (net (code "105") (name "RTS") (class "Default")
      (node (ref "R13") (pin "2") (pinfunction "2_2") (pintype "passive"))
      (node (ref "U3") (pin "6") (pinfunction "RTS#_6") (pintype "bidirectional"))
      (node (ref "U4") (pin "1") (pinfunction "E1_1") (pintype "bidirectional"))
    )
    (net (code "106") (name "RX") (class "Default")
      (node (ref "P9") (pin "P$1") (pinfunction "P$1_P$1") (pintype "bidirectional"))
      (node (ref "U9") (pin "44") (pinfunction "MTCK_44") (pintype "bidirectional"))
    )
    (net (code "107") (name "RXD0_H") (class "Default")
      (node (ref "R11") (pin "1") (pinfunction "1_1") (pintype "passive"))
      (node (ref "U9") (pin "50") (pinfunction "U0RXD_50") (pintype "bidirectional"))
    )
    (net (code "108") (name "SCL") (class "Default")
      (node (ref "P11") (pin "P$1") (pinfunction "P$1_P$1") (pintype "bidirectional"))
      (node (ref "R16") (pin "1") (pinfunction "1_1") (pintype "passive"))
      (node (ref "R24") (pin "1") (pinfunction "1_1") (pintype "passive"))
      (node (ref "R29") (pin "2") (pinfunction "2_2") (pintype "passive"))
      (node (ref "R78") (pin "1") (pinfunction "1_1") (pintype "passive"))
      (node (ref "U9") (pin "8") (pinfunction "GPIO3_8") (pintype "bidirectional"))
    )
    (net (code "109") (name "SDA") (class "Default")
      (node (ref "P14") (pin "P$1") (pinfunction "P$1_P$1") (pintype "bidirectional"))
      (node (ref "R21") (pin "1") (pinfunction "1_1") (pintype "passive"))
      (node (ref "R25") (pin "1") (pinfunction "1_1") (pintype "passive"))
      (node (ref "R26") (pin "2") (pinfunction "2_2") (pintype "passive"))
      (node (ref "R77") (pin "1") (pinfunction "1_1") (pintype "passive"))
      (node (ref "U9") (pin "9") (pinfunction "GPIO4_9") (pintype "bidirectional"))
    )
    (net (code "110") (name "SPICLK") (class "Default")
      (node (ref "U8") (pin "6") (pinfunction "CLK_6") (pintype "bidirectional"))
      (node (ref "U9") (pin "33") (pinfunction "SPICLK_33") (pintype "bidirectional"))
    )
    (net (code "111") (name "SPICS0") (class "Default")
      (node (ref "U8") (pin "1") (pinfunction "/CS_1") (pintype "bidirectional"))
      (node (ref "U9") (pin "32") (pinfunction "SPICS0_32") (pintype "bidirectional"))
    )
    (net (code "112") (name "SPID") (class "Default")
      (node (ref "U8") (pin "5") (pinfunction "DI_(IO0)_5") (pintype "bidirectional"))
      (node (ref "U9") (pin "35") (pinfunction "SPID_35") (pintype "bidirectional"))
    )
    (net (code "113") (name "SPIHD") (class "Default")
      (node (ref "U8") (pin "7") (pinfunction "/HOLD_OR_/RESET_(IO3)_7") (pintype "bidirectional"))
      (node (ref "U9") (pin "30") (pinfunction "SPIHD_30") (pintype "bidirectional"))
    )
    (net (code "114") (name "SPIQ") (class "Default")
      (node (ref "U8") (pin "2") (pinfunction "DO_(IO1)_2") (pintype "bidirectional"))
      (node (ref "U9") (pin "34") (pinfunction "SPIQ_34") (pintype "bidirectional"))
    )
    (net (code "115") (name "SPIWP") (class "Default")
      (node (ref "U8") (pin "3") (pinfunction "/WP_(IO2)_3") (pintype "bidirectional"))
      (node (ref "U9") (pin "31") (pinfunction "SPIWP_31") (pintype "bidirectional"))
    )
    (net (code "116") (name "TE") (class "Default")
      (node (ref "R70") (pin "1") (pinfunction "1_1") (pintype "passive"))
      (node (ref "U9") (pin "27") (pinfunction "GPIO21_27") (pintype "bidirectional"))
    )
    (net (code "117") (name "TOUCH_INT") (class "Default")
      (node (ref "R66") (pin "1") (pinfunction "1_1") (pintype "passive"))
      (node (ref "U9") (pin "7") (pinfunction "GPIO2_7") (pintype "bidirectional"))
    )
    (net (code "118") (name "TOUCH_RST") (class "Default")
      (node (ref "R79") (pin "1") (pinfunction "1_1") (pintype "passive"))
      (node (ref "U9") (pin "10") (pinfunction "GPIO5_10") (pintype "bidirectional"))
    )
    (net (code "119") (name "TX") (class "Default")
      (node (ref "P10") (pin "P$1") (pinfunction "P$1_P$1") (pintype "bidirectional"))
      (node (ref "U9") (pin "43") (pinfunction "GPIO38_43") (pintype "bidirectional"))
    )
    (net (code "120") (name "TXD0_H") (class "Default")
      (node (ref "R10") (pin "1") (pinfunction "1_1") (pintype "passive"))
      (node (ref "U9") (pin "49") (pinfunction "U0TXD_49") (pintype "bidirectional"))
    )
    (net (code "121") (name "USB_D+") (class "Default")
      (node (ref "D1") (pin "2") (pinfunction "2_2") (pintype "bidirectional"))
      (node (ref "R23") (pin "1") (pinfunction "1_1") (pintype "passive"))
      (node (ref "U3") (pin "1") (pinfunction "UD+_1") (pintype "bidirectional"))
    )
    (net (code "122") (name "USB_D-") (class "Default")
      (node (ref "D3") (pin "2") (pinfunction "2_2") (pintype "bidirectional"))
      (node (ref "R18") (pin "1") (pinfunction "1_1") (pintype "passive"))
      (node (ref "U3") (pin "2") (pinfunction "UD-_2") (pintype "bidirectional"))
    )
    (net (code "123") (name "USB_POWER_DET") (class "Default")
      (node (ref "R39") (pin "2") (pinfunction "2_2") (pintype "passive"))
      (node (ref "R40") (pin "2") (pinfunction "2_2") (pintype "passive"))
      (node (ref "U12") (pin "7") (pinfunction "P3.2/SCLK_7") (pintype "bidirectional"))
      (node (ref "U9") (pin "23") (pinfunction "GPIO17_23") (pintype "bidirectional"))
    )
    (net (code "124") (name "VBUS") (class "Default")
      (node (ref "C51") (pin "2") (pinfunction "2_2") (pintype "passive"))
      (node (ref "C9") (pin "1") (pinfunction "1_1") (pintype "passive"))
      (node (ref "D4") (pin "2") (pinfunction "2_2") (pintype "bidirectional"))
      (node (ref "D9") (pin "1") (pinfunction "1_1") (pintype "bidirectional"))
      (node (ref "J3") (pin "A4") (pinfunction "VBUS_A4") (pintype "bidirectional"))
      (node (ref "J3") (pin "A9") (pinfunction "VBUS_A9") (pintype "bidirectional"))
      (node (ref "J3") (pin "B4") (pinfunction "VBUS_B4") (pintype "bidirectional"))
      (node (ref "J3") (pin "B9") (pinfunction "VBUS_B9") (pintype "bidirectional"))
      (node (ref "R37") (pin "2") (pinfunction "2_2") (pintype "passive"))
      (node (ref "R39") (pin "1") (pinfunction "1_1") (pintype "passive"))
      (node (ref "R48") (pin "1") (pinfunction "1_1") (pintype "passive"))
      (node (ref "R5") (pin "1") (pinfunction "1_1") (pintype "passive"))
      (node (ref "U3") (pin "7") (pinfunction "VCC_7") (pintype "bidirectional"))
      (node (ref "U6") (pin "P$4") (pinfunction "VCC_P$4") (pintype "bidirectional"))
      (node (ref "U6") (pin "P$8") (pinfunction "CE_P$8") (pintype "bidirectional"))
    )
    (net (code "125") (name "VCC3V3") (class "Default")
      (node (ref "C18") (pin "2") (pinfunction "2_2") (pintype "passive"))
      (node (ref "C19") (pin "1") (pinfunction "1_1") (pintype "passive"))
      (node (ref "C23") (pin "1") (pinfunction "1_1") (pintype "passive"))
      (node (ref "C31") (pin "1") (pinfunction "1_1") (pintype "passive"))
      (node (ref "L4") (pin "2") (pinfunction "2_2") (pintype "passive"))
      (node (ref "P1") (pin "P$1") (pinfunction "P$1_P$1") (pintype "bidirectional"))
      (node (ref "P15") (pin "P$1") (pinfunction "P$1_P$1") (pintype "bidirectional"))
      (node (ref "Q7") (pin "3") (pinfunction "D_3") (pintype "passive"))
      (node (ref "R14") (pin "1") (pinfunction "1_1") (pintype "passive"))
      (node (ref "R26") (pin "1") (pinfunction "1_1") (pintype "passive"))
      (node (ref "R29") (pin "1") (pinfunction "1_1") (pintype "passive"))
      (node (ref "R6") (pin "1") (pinfunction "1_1") (pintype "passive"))
      (node (ref "R62") (pin "1") (pinfunction "1_1") (pintype "passive"))
      (node (ref "R63") (pin "1") (pinfunction "1_1") (pintype "passive"))
      (node (ref "R65") (pin "1") (pinfunction "1_1") (pintype "passive"))
      (node (ref "U10") (pin "16") (pinfunction "VDDA_16") (pintype "bidirectional"))
      (node (ref "U9") (pin "20") (pinfunction "VDD3P3_RTC_20") (pintype "bidirectional"))
      (node (ref "U9") (pin "46") (pinfunction "VDD3P3_CPU_46") (pintype "bidirectional"))
      (node (ref "U9") (pin "55") (pinfunction "VDDA_1_55") (pintype "bidirectional"))
      (node (ref "U9") (pin "56") (pinfunction "VDDA_2_56") (pintype "bidirectional"))
    )
    (net (code "126") (name "VDD3V3") (class "Default")
      (node (ref "C24") (pin "1") (pinfunction "1_1") (pintype "passive"))
      (node (ref "C28") (pin "1") (pinfunction "1_1") (pintype "passive"))
      (node (ref "C37") (pin "2") (pinfunction "2_2") (pintype "passive"))
      (node (ref "C38") (pin "2") (pinfunction "2_2") (pintype "passive"))
      (node (ref "C39") (pin "2") (pinfunction "2_2") (pintype "passive"))
      (node (ref "P4") (pin "P$1") (pinfunction "P$1_P$1") (pintype "bidirectional"))
      (node (ref "Q7") (pin "2") (pinfunction "S_2") (pintype "passive"))
      (node (ref "R601") (pin "2") (pinfunction "2_2") (pintype "passive"))
      (node (ref "R9") (pin "1") (pinfunction "1_1") (pintype "passive"))
      (node (ref "U1") (pin "P$8") (pinfunction "VDD_P$8") (pintype "bidirectional"))
      (node (ref "U12") (pin "2") (pinfunction "VCC_2") (pintype "bidirectional"))
      (node (ref "U5") (pin "P$5") (pinfunction "OUT_P$5") (pintype "bidirectional"))
    )
    (net (code "127") (name "VDD_SPI") (class "Default")
      (node (ref "C20") (pin "2") (pinfunction "2_2") (pintype "passive"))
      (node (ref "U8") (pin "8") (pinfunction "VCC_8") (pintype "bidirectional"))
      (node (ref "U9") (pin "29") (pinfunction "VDD_SPI_29") (pintype "bidirectional"))
    )
    (net (code "128") (name "VIB_EN") (class "Default")
      (node (ref "R2") (pin "1") (pinfunction "1_1") (pintype "passive"))
      (node (ref "U9") (pin "51") (pinfunction "GPIO45_51") (pintype "bidirectional"))
    )
    (net (code "129") (name "VIN") (class "Default")
      (node (ref "C13") (pin "2") (pinfunction "2_2") (pintype "passive"))
      (node (ref "C34") (pin "2") (pinfunction "2_2") (pintype "passive"))
      (node (ref "C35") (pin "2") (pinfunction "2_2") (pintype "passive"))
      (node (ref "C6") (pin "2") (pinfunction "2_2") (pintype "passive"))
      (node (ref "D9") (pin "2") (pinfunction "2_2") (pintype "bidirectional"))
      (node (ref "Q5") (pin "2") (pinfunction "S_2") (pintype "bidirectional"))
      (node (ref "U13") (pin "4") (pinfunction "VIN_4") (pintype "input"))
      (node (ref "U5") (pin "P$1") (pinfunction "IN_P$1") (pintype "bidirectional"))
      (node (ref "U5") (pin "P$3") (pinfunction "EN_P$3") (pintype "bidirectional"))
    )
    (net (code "130") (name "unconnected-(ANT1-PadP$2)") (class "Default")
      (node (ref "ANT1") (pin "P$2") (pinfunction "P$2_P$2") (pintype "bidirectional"))
    )
    (net (code "131") (name "unconnected-(FPC2-Pad8)") (class "Default")
      (node (ref "FPC2") (pin "8") (pinfunction "8_8") (pintype "bidirectional"))
    )
    (net (code "132") (name "unconnected-(J3-SBU1-PadA8)") (class "Default")
      (node (ref "J3") (pin "A8") (pinfunction "SBU1_A8") (pintype "bidirectional"))
    )
    (net (code "133") (name "unconnected-(J3-SBU2-PadB8)") (class "Default")
      (node (ref "J3") (pin "B8") (pinfunction "SBU2_B8") (pintype "bidirectional"))
    )
    (net (code "134") (name "unconnected-(U1-CLKOUT-PadP$7)") (class "Default")
      (node (ref "U1") (pin "P$7") (pinfunction "CLKOUT_P$7") (pintype "bidirectional"))
    )
    (net (code "135") (name "unconnected-(U1-INT#-PadP$3)") (class "Default")
      (node (ref "U1") (pin "P$3") (pinfunction "INT#_P$3") (pintype "bidirectional"))
    )
    (net (code "136") (name "unconnected-(U3-CTS#-Pad5)") (class "Default")
      (node (ref "U3") (pin "5") (pinfunction "CTS#_5") (pintype "bidirectional"))
    )
    (net (code "137") (name "unconnected-(U5-BP{slash}FB-PadP$4)") (class "Default")
      (node (ref "U5") (pin "P$4") (pinfunction "BP/FB_P$4") (pintype "bidirectional"))
    )
    (net (code "138") (name "unconnected-(U7-INT1-PadP$5)") (class "Default")
      (node (ref "U7") (pin "P$5") (pinfunction "INT1_P$5") (pintype "bidirectional"))
    )
    (net (code "139") (name "unconnected-(U7-INT2-PadP$6)") (class "Default")
      (node (ref "U7") (pin "P$6") (pinfunction "INT2_P$6") (pintype "bidirectional"))
    )
    (net (code "140") (name "unconnected-(U7-NC2-PadP$11)") (class "Default")
      (node (ref "U7") (pin "P$11") (pinfunction "NC2_P$11") (pintype "bidirectional"))
    )
    (net (code "141") (name "unconnected-(U7-SDO-PadP$1)") (class "Default")
      (node (ref "U7") (pin "P$1") (pinfunction "SDO_P$1") (pintype "bidirectional"))
    )
    (net (code "142") (name "unconnected-(U9-GPIO33-Pad38)") (class "Default")
      (node (ref "U9") (pin "38") (pinfunction "GPIO33_38") (pintype "bidirectional"))
    )
    (net (code "143") (name "unconnected-(U9-GPIO34-Pad39)") (class "Default")
      (node (ref "U9") (pin "39") (pinfunction "GPIO34_39") (pintype "bidirectional"))
    )
    (net (code "144") (name "unconnected-(U9-GPIO35-Pad40)") (class "Default")
      (node (ref "U9") (pin "40") (pinfunction "GPIO35_40") (pintype "bidirectional"))
    )
    (net (code "145") (name "unconnected-(U9-GPIO36-Pad41)") (class "Default")
      (node (ref "U9") (pin "41") (pinfunction "GPIO36_41") (pintype "bidirectional"))
    )
    (net (code "146") (name "unconnected-(U9-GPIO37-Pad42)") (class "Default")
      (node (ref "U9") (pin "42") (pinfunction "GPIO37_42") (pintype "bidirectional"))
    )
    (net (code "147") (name "unconnected-(U9-SPICS1-Pad28)") (class "Default")
      (node (ref "U9") (pin "28") (pinfunction "SPICS1_28") (pintype "bidirectional"))
    )
    (net (code "148") (name "unconnected-(U10-S13-Pad14)") (class "Default")
      (node (ref "U10") (pin "14") (pinfunction "S13_14") (pintype "bidirectional"))
    )
  )
)
